# clouds_v30.net
KiCad netlist of a schematic drawn in EAGLE
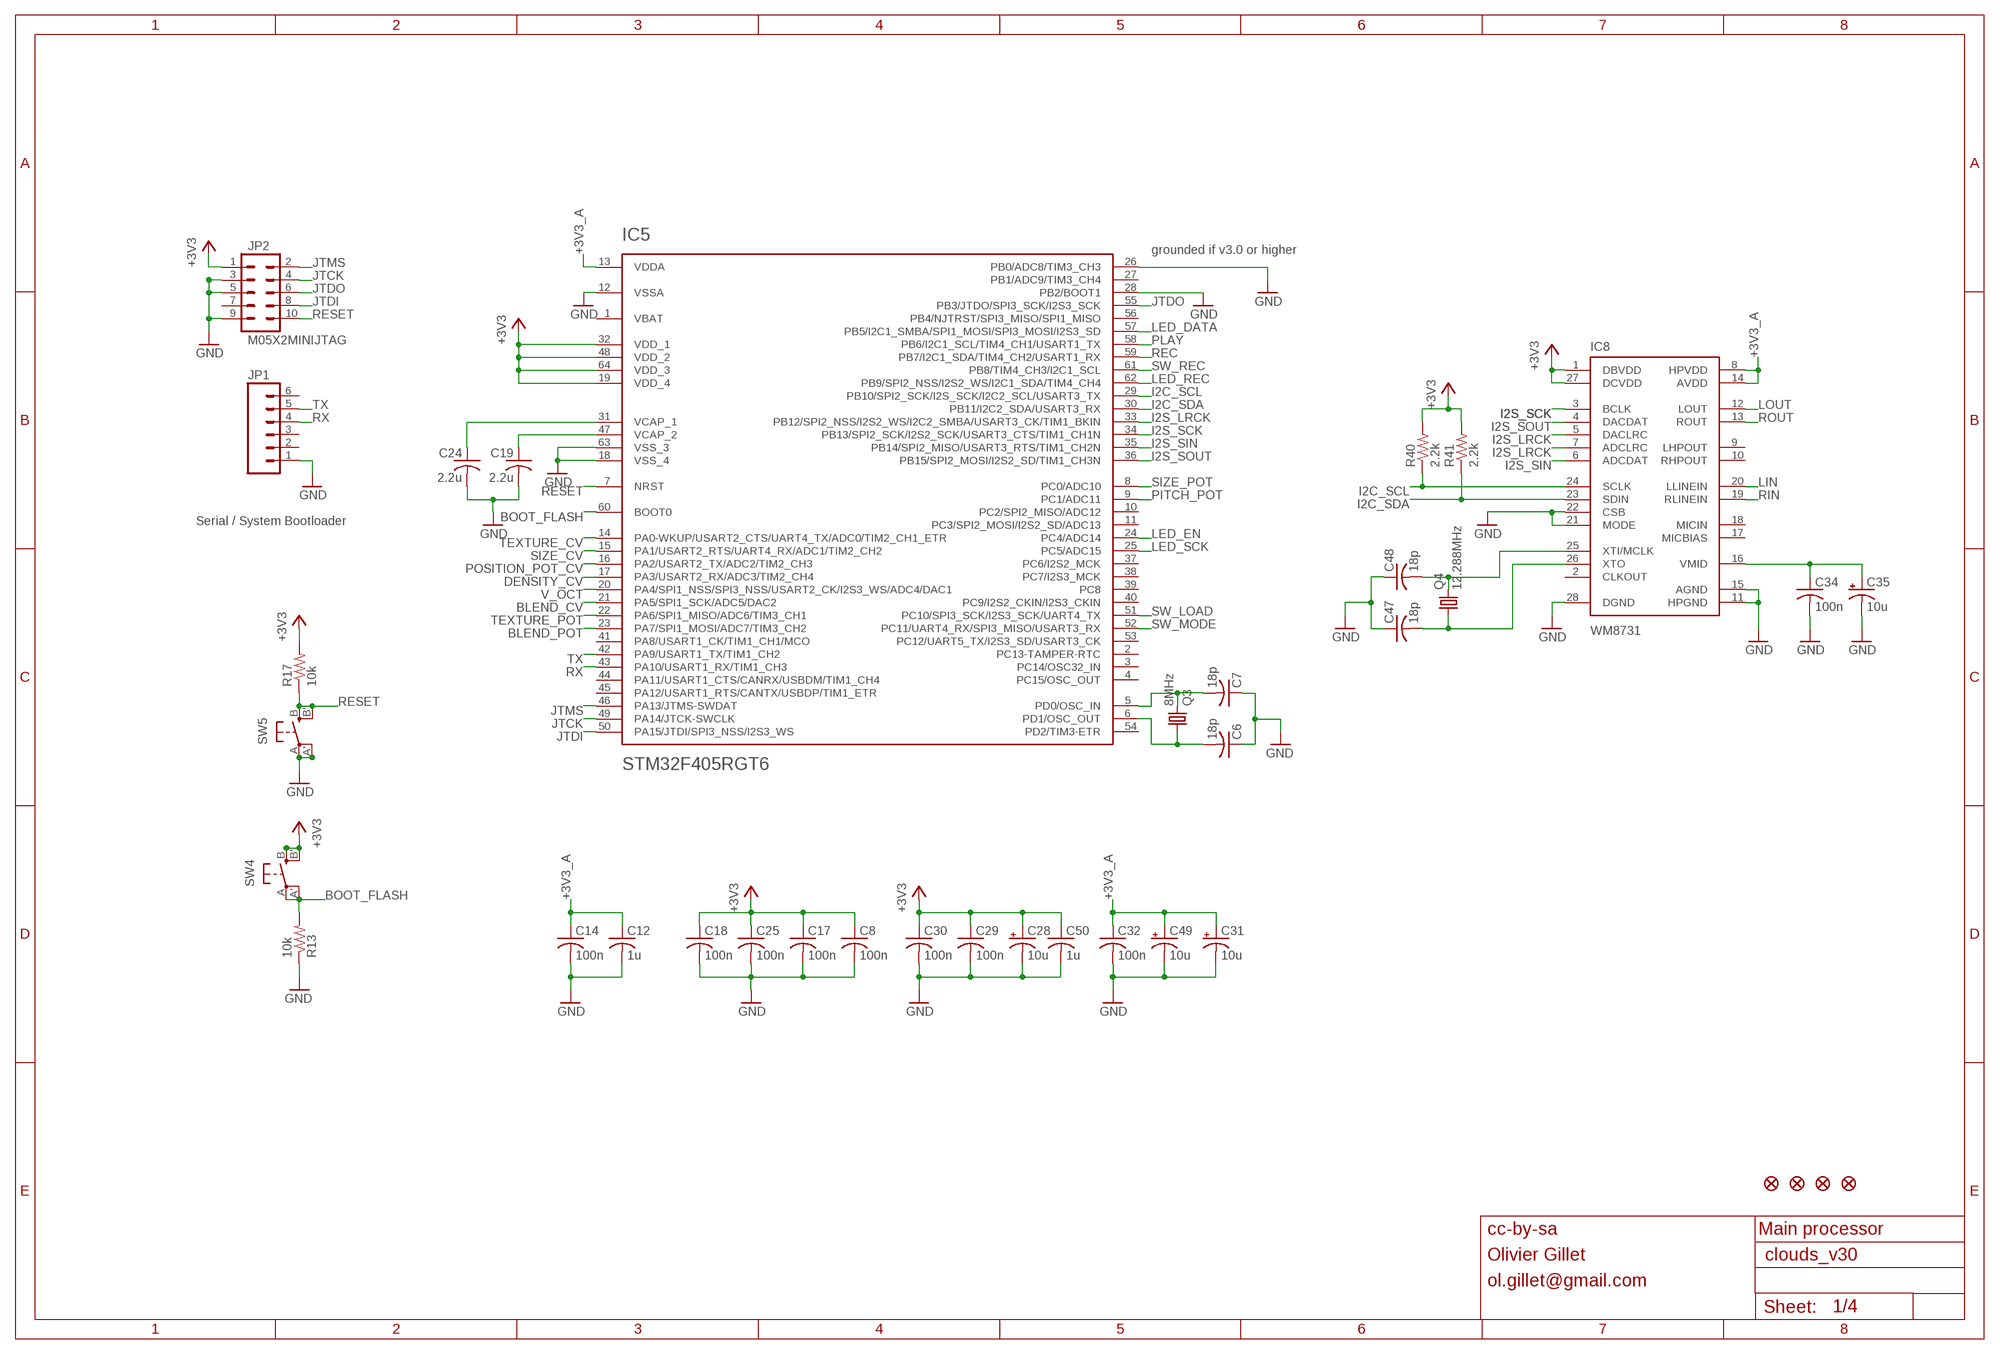
[diagram p0: schematic, sheet 1]
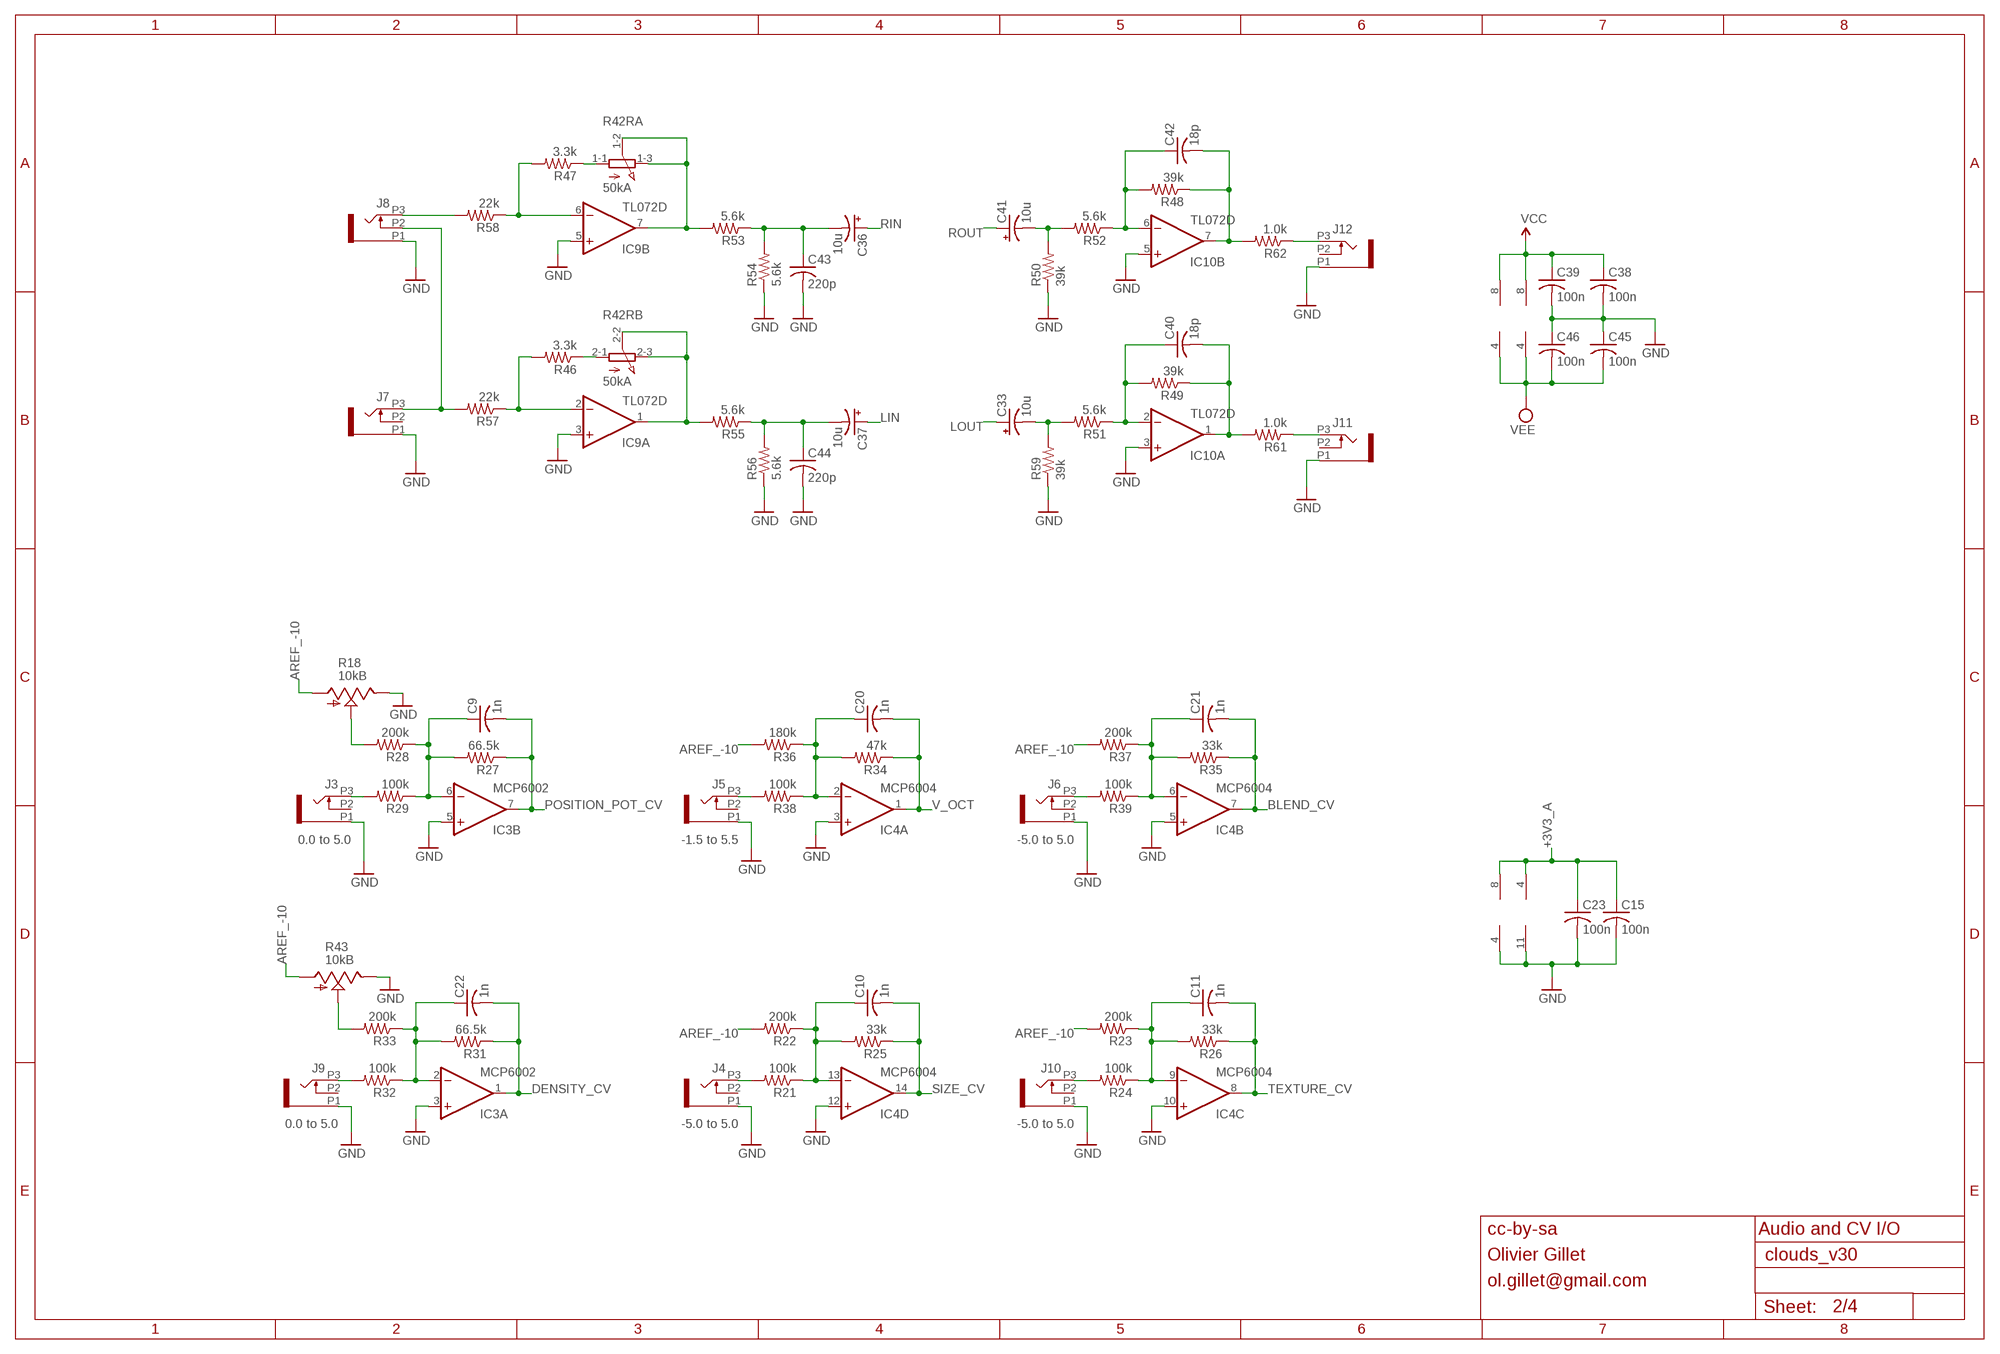
[diagram p1: schematic, sheet 2]
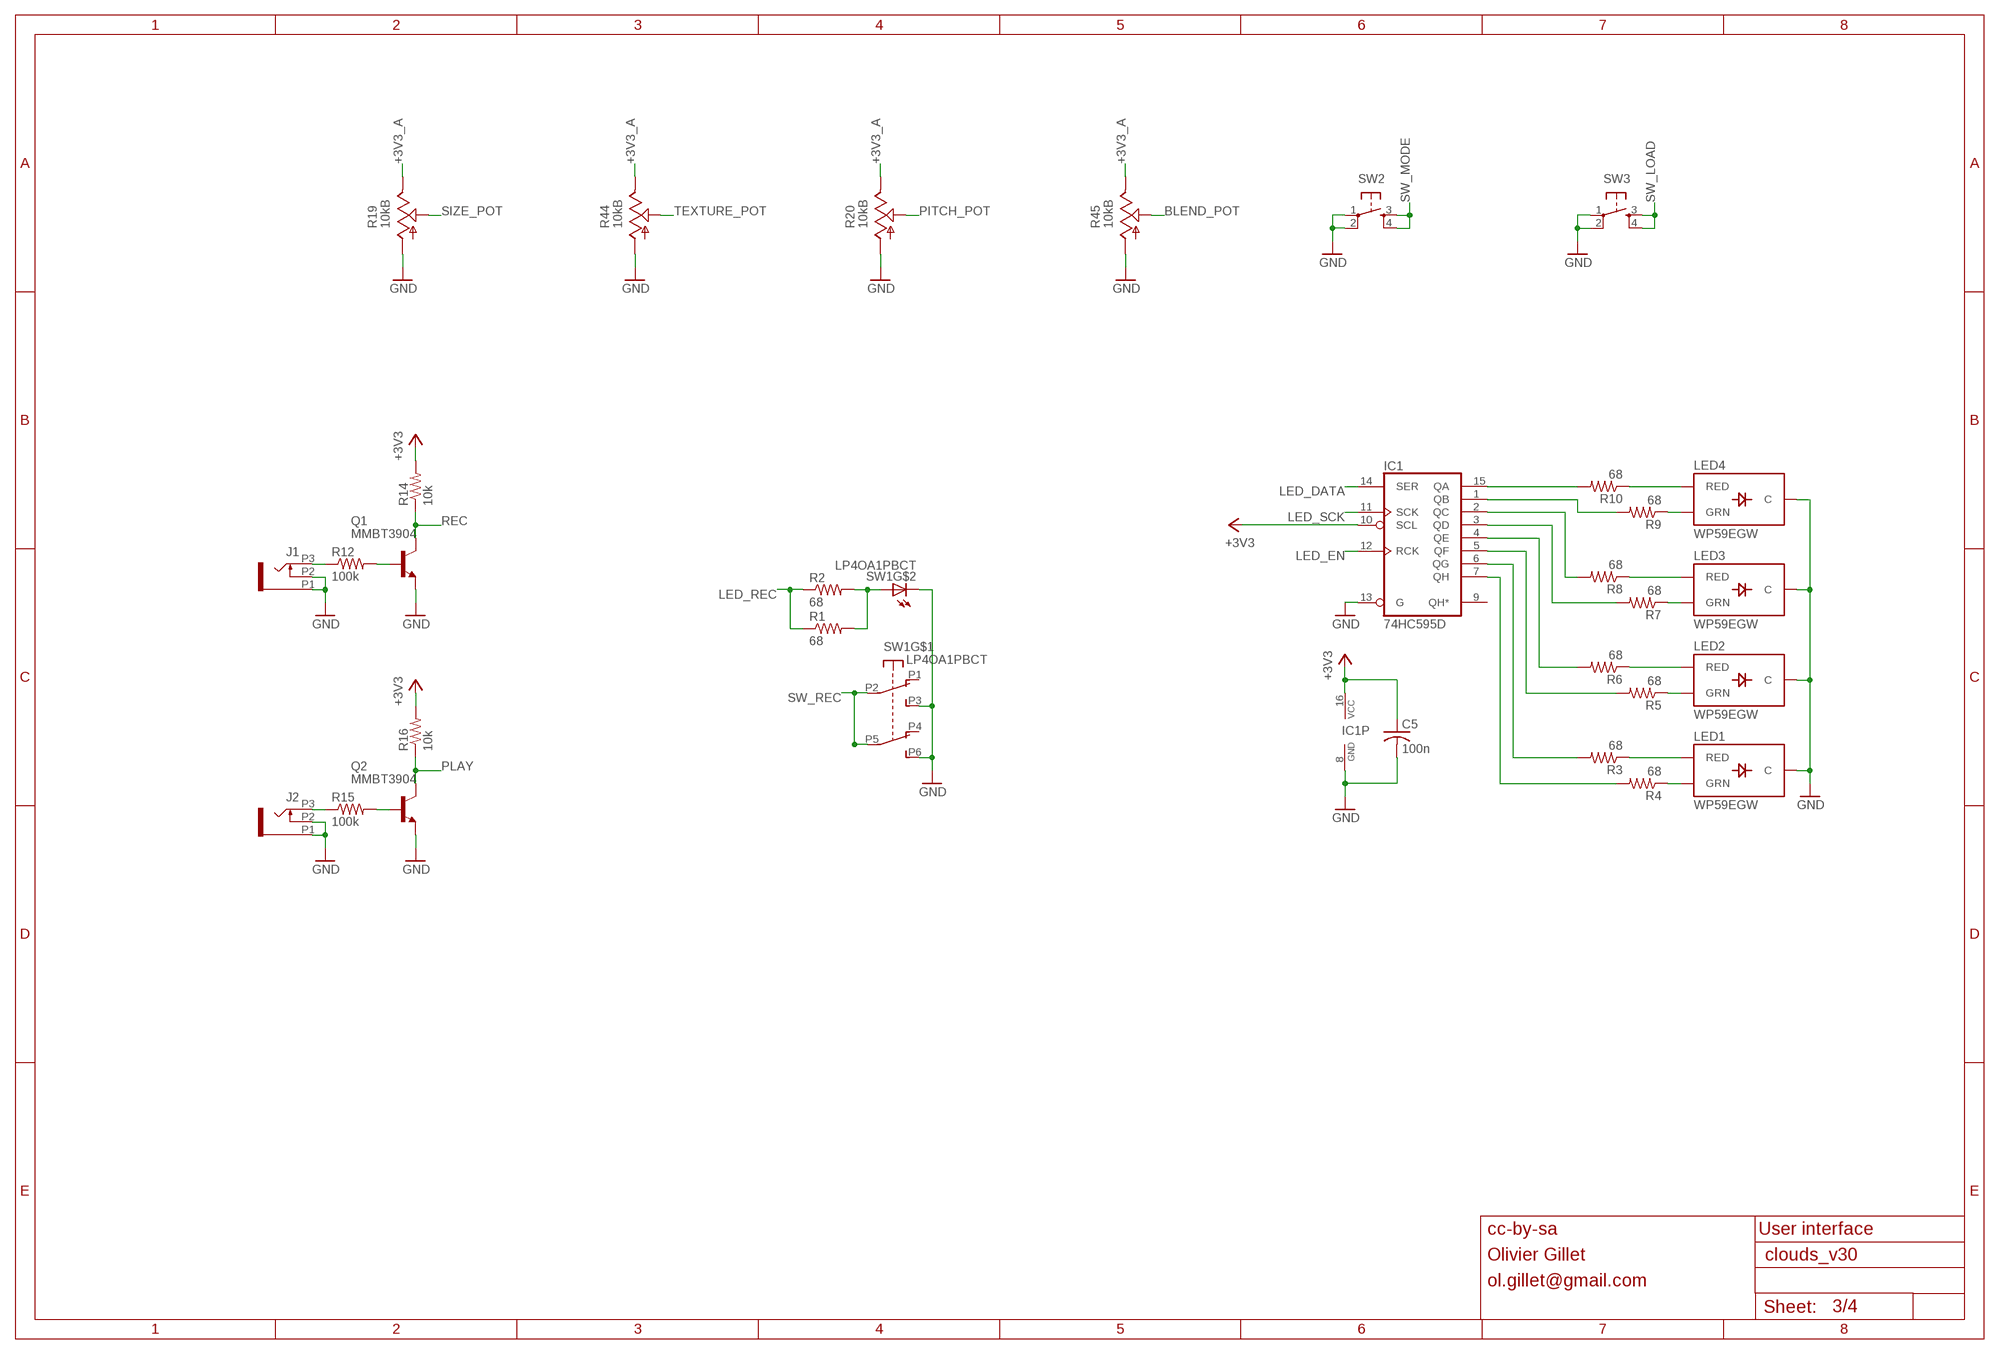
[diagram p2: schematic, sheet 3]
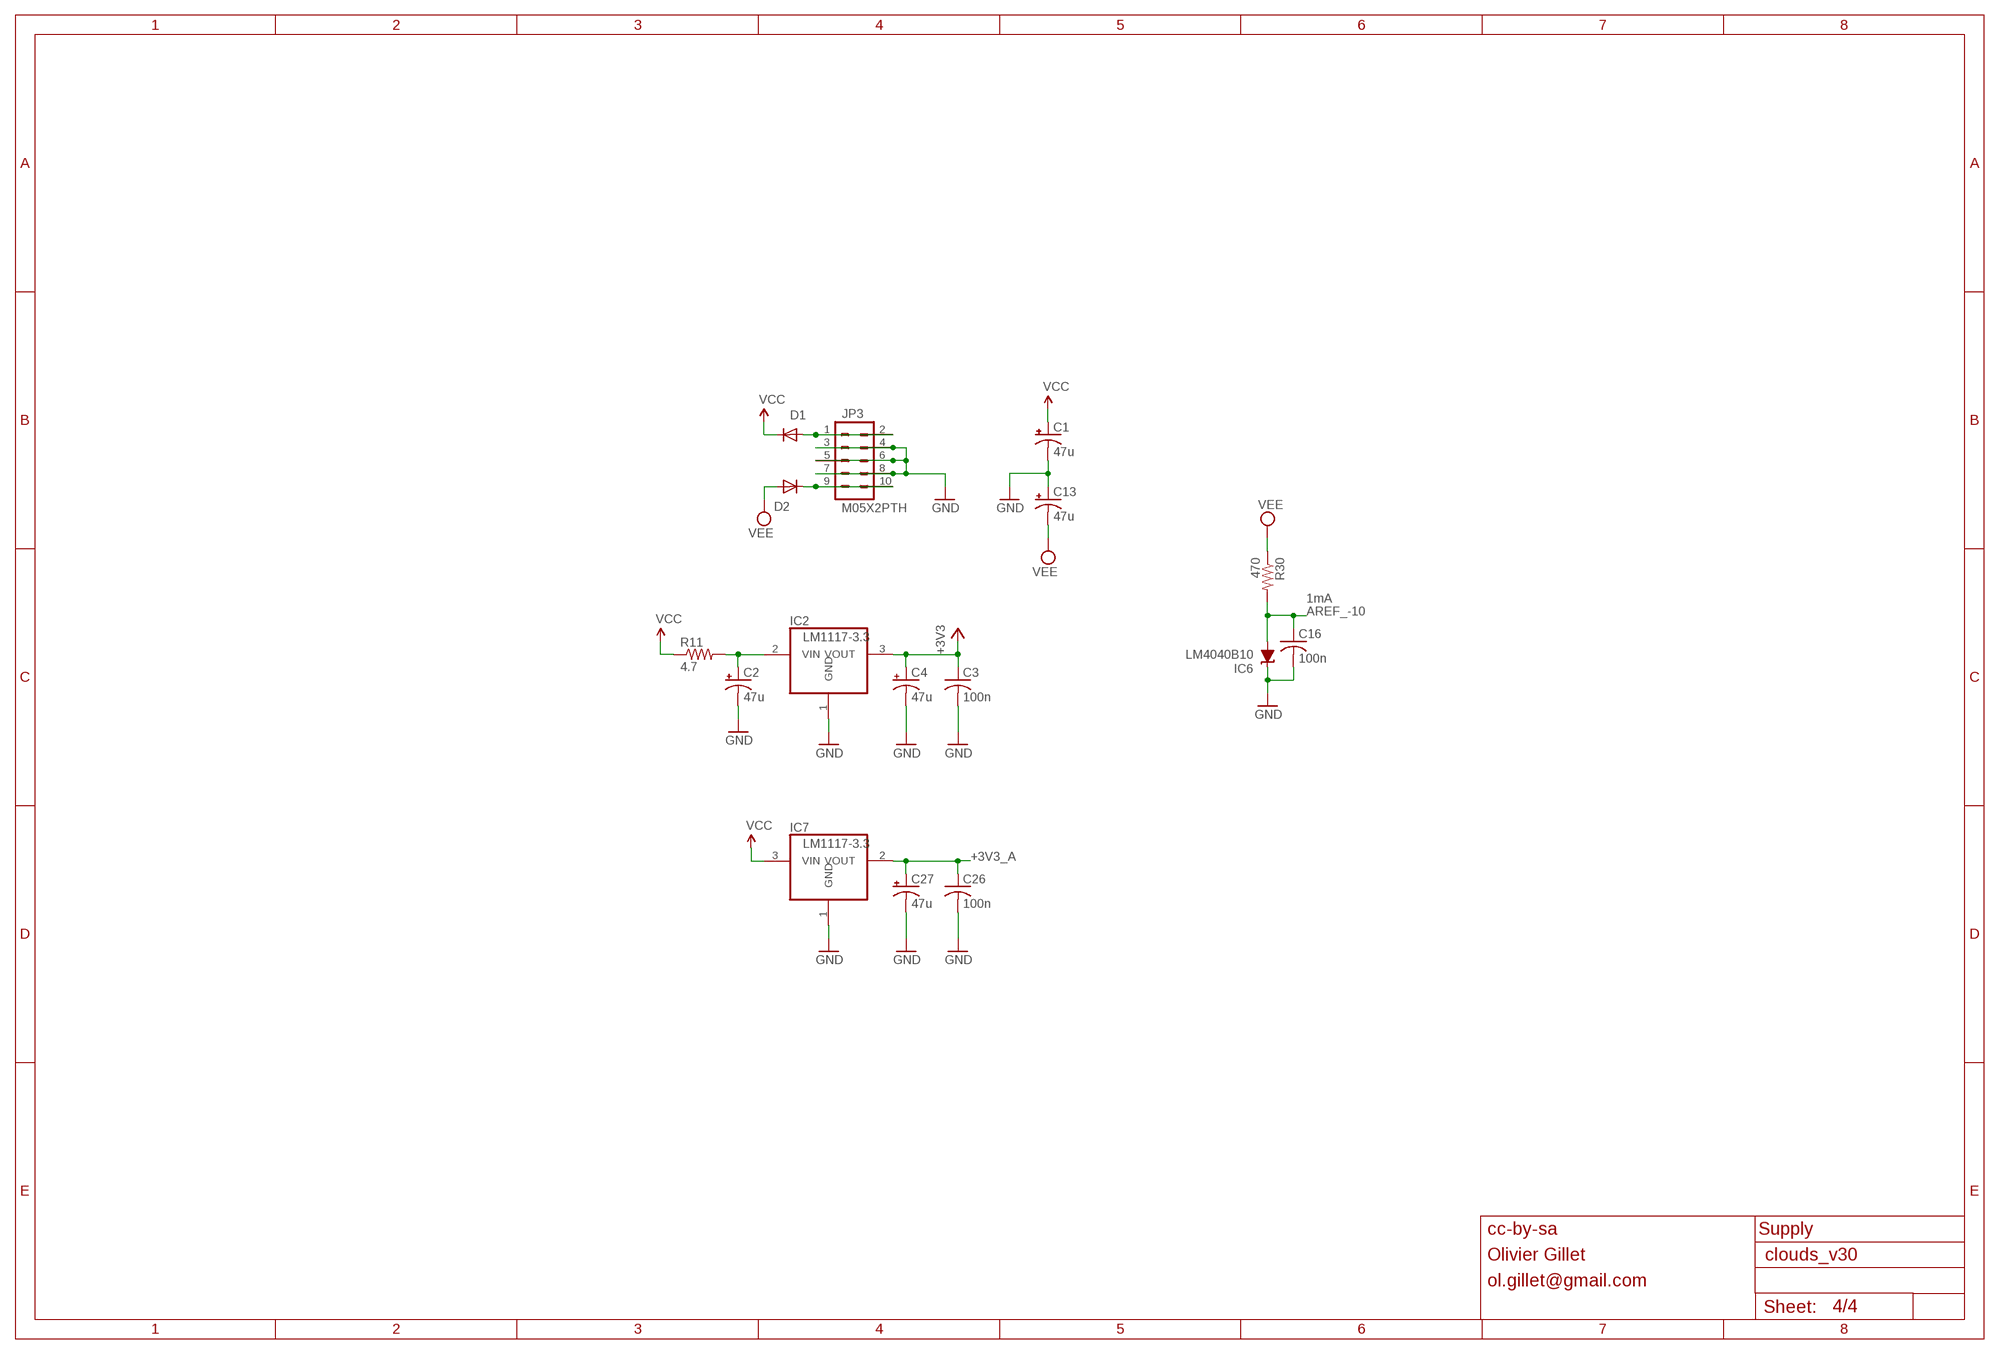
[diagram p3: schematic, sheet 4]

(export (version "E")
  (design (tool "Eeschema 10.0.6"))
  (components
    (comp (ref "C9")
      (value "1n")
      (footprint "eagle-import:C0603")
      (libsource (lib "eagle-import") (part "C-USC0603"))
    )
    (comp (ref "C10")
      (value "1n")
      (footprint "eagle-import:C0603")
      (libsource (lib "eagle-import") (part "C-USC0603"))
    )
    (comp (ref "C11")
      (value "1n")
      (footprint "eagle-import:C0603")
      (libsource (lib "eagle-import") (part "C-USC0603"))
    )
    (comp (ref "C15")
      (value "100n")
      (footprint "eagle-import:C0603")
      (libsource (lib "eagle-import") (part "C-USC0603"))
    )
    (comp (ref "C20")
      (value "1n")
      (footprint "eagle-import:C0603")
      (libsource (lib "eagle-import") (part "C-USC0603"))
    )
    (comp (ref "C21")
      (value "1n")
      (footprint "eagle-import:C0603")
      (libsource (lib "eagle-import") (part "C-USC0603"))
    )
    (comp (ref "C22")
      (value "1n")
      (footprint "eagle-import:C0603")
      (libsource (lib "eagle-import") (part "C-USC0603"))
    )
    (comp (ref "C23")
      (value "100n")
      (footprint "eagle-import:C0603")
      (libsource (lib "eagle-import") (part "C-USC0603"))
    )
    (comp (ref "C33")
      (value "10u")
      (footprint "eagle-import:PANASONIC_B")
      (libsource (lib "eagle-import") (part "CPOL-USB"))
    )
    (comp (ref "C36")
      (value "10u")
      (footprint "eagle-import:PANASONIC_B")
      (libsource (lib "eagle-import") (part "CPOL-USB"))
    )
    (comp (ref "C37")
      (value "10u")
      (footprint "eagle-import:PANASONIC_B")
      (libsource (lib "eagle-import") (part "CPOL-USB"))
    )
    (comp (ref "C38")
      (value "100n")
      (footprint "eagle-import:C0603")
      (libsource (lib "eagle-import") (part "C-USC0603"))
    )
    (comp (ref "C39")
      (value "100n")
      (footprint "eagle-import:C0603")
      (libsource (lib "eagle-import") (part "C-USC0603"))
    )
    (comp (ref "C40")
      (value "18p")
      (footprint "eagle-import:C0603")
      (libsource (lib "eagle-import") (part "C-USC0603"))
    )
    (comp (ref "C41")
      (value "10u")
      (footprint "eagle-import:PANASONIC_B")
      (libsource (lib "eagle-import") (part "CPOL-USB"))
    )
    (comp (ref "C42")
      (value "18p")
      (footprint "eagle-import:C0603")
      (libsource (lib "eagle-import") (part "C-USC0603"))
    )
    (comp (ref "C43")
      (value "220p")
      (footprint "eagle-import:C0603")
      (libsource (lib "eagle-import") (part "C-USC0603"))
    )
    (comp (ref "C44")
      (value "220p")
      (footprint "eagle-import:C0603")
      (libsource (lib "eagle-import") (part "C-USC0603"))
    )
    (comp (ref "C45")
      (value "100n")
      (footprint "eagle-import:C0603")
      (libsource (lib "eagle-import") (part "C-USC0603"))
    )
    (comp (ref "C46")
      (value "100n")
      (footprint "eagle-import:C0603")
      (libsource (lib "eagle-import") (part "C-USC0603"))
    )
    (comp (ref "IC3")
      (value "MCP6002")
      (footprint "eagle-import:SO08")
      (libsource (lib "eagle-import") (part "TL072D"))
    )
    (comp (ref "IC4")
      (value "MCP6004")
      (footprint "eagle-import:SO14")
      (libsource (lib "eagle-import") (part "TL074D"))
    )
    (comp (ref "IC9")
      (value "TL072D")
      (footprint "eagle-import:SO08")
      (libsource (lib "eagle-import") (part "og-linear_TL072D"))
    )
    (comp (ref "IC10")
      (value "TL072D")
      (footprint "eagle-import:SO08")
      (libsource (lib "eagle-import") (part "og-linear_TL072D"))
    )
    (comp (ref "J3")
      (value "PJ301_THONKICONN6")
      (footprint "eagle-import:WQP_PJ_301M6")
      (libsource (lib "eagle-import") (part "PJ301_THONKICONN6"))
    )
    (comp (ref "J4")
      (value "PJ301_THONKICONN6")
      (footprint "eagle-import:WQP_PJ_301M6")
      (libsource (lib "eagle-import") (part "PJ301_THONKICONN6"))
    )
    (comp (ref "J5")
      (value "PJ301_THONKICONN6")
      (footprint "eagle-import:WQP_PJ_301M6")
      (libsource (lib "eagle-import") (part "PJ301_THONKICONN6"))
    )
    (comp (ref "J6")
      (value "PJ301_THONKICONN6")
      (footprint "eagle-import:WQP_PJ_301M6")
      (libsource (lib "eagle-import") (part "PJ301_THONKICONN6"))
    )
    (comp (ref "J7")
      (value "PJ301_THONKICONN6")
      (footprint "eagle-import:WQP_PJ_301M6")
      (libsource (lib "eagle-import") (part "PJ301_THONKICONN6"))
    )
    (comp (ref "J8")
      (value "PJ301_THONKICONN6")
      (footprint "eagle-import:WQP_PJ_301M6")
      (libsource (lib "eagle-import") (part "PJ301_THONKICONN6"))
    )
    (comp (ref "J9")
      (value "PJ301_THONKICONN6")
      (footprint "eagle-import:WQP_PJ_301M6")
      (libsource (lib "eagle-import") (part "PJ301_THONKICONN6"))
    )
    (comp (ref "J10")
      (value "PJ301_THONKICONN6")
      (footprint "eagle-import:WQP_PJ_301M6")
      (libsource (lib "eagle-import") (part "PJ301_THONKICONN6"))
    )
    (comp (ref "J11")
      (value "PJ301_THONKICONN6")
      (footprint "eagle-import:WQP_PJ_301M6")
      (libsource (lib "eagle-import") (part "PJ301_THONKICONN6"))
    )
    (comp (ref "J12")
      (value "PJ301_THONKICONN6")
      (footprint "eagle-import:WQP_PJ_301M6")
      (libsource (lib "eagle-import") (part "PJ301_THONKICONN6"))
    )
    (comp (ref "R18")
      (value "10kB")
      (footprint "eagle-import:ALPS_POT_VERTICAL_PS")
      (libsource (lib "eagle-import") (part "POT_USVERTICAL_PS"))
    )
    (comp (ref "R21")
      (value "100k")
      (footprint "eagle-import:R0603")
      (libsource (lib "eagle-import") (part "R-US_R0603"))
    )
    (comp (ref "R22")
      (value "200k")
      (footprint "eagle-import:R0603")
      (libsource (lib "eagle-import") (part "R-US_R0603"))
    )
    (comp (ref "R23")
      (value "200k")
      (footprint "eagle-import:R0603")
      (libsource (lib "eagle-import") (part "R-US_R0603"))
    )
    (comp (ref "R24")
      (value "100k")
      (footprint "eagle-import:R0603")
      (libsource (lib "eagle-import") (part "R-US_R0603"))
    )
    (comp (ref "R25")
      (value "33k")
      (footprint "eagle-import:R0603")
      (libsource (lib "eagle-import") (part "R-US_R0603"))
    )
    (comp (ref "R26")
      (value "33k")
      (footprint "eagle-import:R0603")
      (libsource (lib "eagle-import") (part "R-US_R0603"))
    )
    (comp (ref "R27")
      (value "66.5k")
      (footprint "eagle-import:R0603")
      (libsource (lib "eagle-import") (part "R-US_R0603"))
    )
    (comp (ref "R28")
      (value "200k")
      (footprint "eagle-import:R0603")
      (libsource (lib "eagle-import") (part "R-US_R0603"))
    )
    (comp (ref "R29")
      (value "100k")
      (footprint "eagle-import:R0603")
      (libsource (lib "eagle-import") (part "R-US_R0603"))
    )
    (comp (ref "R31")
      (value "66.5k")
      (footprint "eagle-import:R0603")
      (libsource (lib "eagle-import") (part "R-US_R0603"))
    )
    (comp (ref "R32")
      (value "100k")
      (footprint "eagle-import:R0603")
      (libsource (lib "eagle-import") (part "R-US_R0603"))
    )
    (comp (ref "R33")
      (value "200k")
      (footprint "eagle-import:R0603")
      (libsource (lib "eagle-import") (part "R-US_R0603"))
    )
    (comp (ref "R34")
      (value "47k")
      (footprint "eagle-import:R0603")
      (libsource (lib "eagle-import") (part "R-US_R0603"))
    )
    (comp (ref "R35")
      (value "33k")
      (footprint "eagle-import:R0603")
      (libsource (lib "eagle-import") (part "R-US_R0603"))
    )
    (comp (ref "R36")
      (value "180k")
      (footprint "eagle-import:R0603")
      (libsource (lib "eagle-import") (part "R-US_R0603"))
    )
    (comp (ref "R37")
      (value "200k")
      (footprint "eagle-import:R0603")
      (libsource (lib "eagle-import") (part "R-US_R0603"))
    )
    (comp (ref "R38")
      (value "100k")
      (footprint "eagle-import:R0603")
      (libsource (lib "eagle-import") (part "R-US_R0603"))
    )
    (comp (ref "R39")
      (value "100k")
      (footprint "eagle-import:R0603")
      (libsource (lib "eagle-import") (part "R-US_R0603"))
    )
    (comp (ref "R42")
      (value "50kA")
      (footprint "eagle-import:ALPHA_RD902F-040")
      (libsource (lib "eagle-import") (part "RD902F-040"))
    )
    (comp (ref "R43")
      (value "10kB")
      (footprint "eagle-import:ALPS_POT_VERTICAL_PS")
      (libsource (lib "eagle-import") (part "POT_USVERTICAL_PS"))
    )
    (comp (ref "R46")
      (value "3.3k")
      (footprint "eagle-import:R0603")
      (libsource (lib "eagle-import") (part "R-US_R0603"))
    )
    (comp (ref "R47")
      (value "3.3k")
      (footprint "eagle-import:R0603")
      (libsource (lib "eagle-import") (part "R-US_R0603"))
    )
    (comp (ref "R48")
      (value "39k")
      (footprint "eagle-import:R0603")
      (libsource (lib "eagle-import") (part "R-US_R0603"))
    )
    (comp (ref "R49")
      (value "39k")
      (footprint "eagle-import:R0603")
      (libsource (lib "eagle-import") (part "R-US_R0603"))
    )
    (comp (ref "R50")
      (value "39k")
      (footprint "eagle-import:R0603")
      (libsource (lib "eagle-import") (part "R-US_R0603"))
    )
    (comp (ref "R51")
      (value "5.6k")
      (footprint "eagle-import:R0603")
      (libsource (lib "eagle-import") (part "R-US_R0603"))
    )
    (comp (ref "R52")
      (value "5.6k")
      (footprint "eagle-import:R0603")
      (libsource (lib "eagle-import") (part "R-US_R0603"))
    )
    (comp (ref "R53")
      (value "5.6k")
      (footprint "eagle-import:R0603")
      (libsource (lib "eagle-import") (part "R-US_R0603"))
    )
    (comp (ref "R54")
      (value "5.6k")
      (footprint "eagle-import:R0603")
      (libsource (lib "eagle-import") (part "R-US_R0603"))
    )
    (comp (ref "R55")
      (value "5.6k")
      (footprint "eagle-import:R0603")
      (libsource (lib "eagle-import") (part "R-US_R0603"))
    )
    (comp (ref "R56")
      (value "5.6k")
      (footprint "eagle-import:R0603")
      (libsource (lib "eagle-import") (part "R-US_R0603"))
    )
    (comp (ref "R57")
      (value "22k")
      (footprint "eagle-import:R0603")
      (libsource (lib "eagle-import") (part "R-US_R0603"))
    )
    (comp (ref "R58")
      (value "22k")
      (footprint "eagle-import:R0603")
      (libsource (lib "eagle-import") (part "R-US_R0603"))
    )
    (comp (ref "R59")
      (value "39k")
      (footprint "eagle-import:R0603")
      (libsource (lib "eagle-import") (part "R-US_R0603"))
    )
    (comp (ref "R61")
      (value "1.0k")
      (footprint "eagle-import:R0603")
      (libsource (lib "eagle-import") (part "R-US_R0603"))
    )
    (comp (ref "R62")
      (value "1.0k")
      (footprint "eagle-import:R0603")
      (libsource (lib "eagle-import") (part "R-US_R0603"))
    )
    (comp (ref "C6")
      (value "18p")
      (footprint "eagle-import:C0603")
      (libsource (lib "eagle-import") (part "C-USC0603"))
    )
    (comp (ref "C7")
      (value "18p")
      (footprint "eagle-import:C0603")
      (libsource (lib "eagle-import") (part "C-USC0603"))
    )
    (comp (ref "C8")
      (value "100n")
      (footprint "eagle-import:C0603")
      (libsource (lib "eagle-import") (part "C-USC0603"))
    )
    (comp (ref "C12")
      (value "1u")
      (footprint "eagle-import:C0603")
      (libsource (lib "eagle-import") (part "C-USC0603"))
    )
    (comp (ref "C14")
      (value "100n")
      (footprint "eagle-import:C0603")
      (libsource (lib "eagle-import") (part "C-USC0603"))
    )
    (comp (ref "C17")
      (value "100n")
      (footprint "eagle-import:C0603")
      (libsource (lib "eagle-import") (part "C-USC0603"))
    )
    (comp (ref "C18")
      (value "100n")
      (footprint "eagle-import:C0603")
      (libsource (lib "eagle-import") (part "C-USC0603"))
    )
    (comp (ref "C19")
      (value "2.2u")
      (footprint "eagle-import:C0805")
      (libsource (lib "eagle-import") (part "C-USC0805"))
    )
    (comp (ref "C24")
      (value "2.2u")
      (footprint "eagle-import:C0805")
      (libsource (lib "eagle-import") (part "C-USC0805"))
    )
    (comp (ref "C25")
      (value "100n")
      (footprint "eagle-import:C0603")
      (libsource (lib "eagle-import") (part "C-USC0603"))
    )
    (comp (ref "C28")
      (value "10u")
      (footprint "eagle-import:PANASONIC_A")
      (libsource (lib "eagle-import") (part "CPOL-USA"))
    )
    (comp (ref "C29")
      (value "100n")
      (footprint "eagle-import:C0603")
      (libsource (lib "eagle-import") (part "C-USC0603"))
    )
    (comp (ref "C30")
      (value "100n")
      (footprint "eagle-import:C0603")
      (libsource (lib "eagle-import") (part "C-USC0603"))
    )
    (comp (ref "C31")
      (value "10u")
      (footprint "eagle-import:PANASONIC_B")
      (libsource (lib "eagle-import") (part "CPOL-USB"))
    )
    (comp (ref "C32")
      (value "100n")
      (footprint "eagle-import:C0603")
      (libsource (lib "eagle-import") (part "C-USC0603"))
    )
    (comp (ref "C34")
      (value "100n")
      (footprint "eagle-import:C0603")
      (libsource (lib "eagle-import") (part "C-USC0603"))
    )
    (comp (ref "C35")
      (value "10u")
      (footprint "eagle-import:PANASONIC_B")
      (libsource (lib "eagle-import") (part "CPOL-USB"))
    )
    (comp (ref "C47")
      (value "18p")
      (footprint "eagle-import:C0603")
      (libsource (lib "eagle-import") (part "C-USC0603"))
    )
    (comp (ref "C48")
      (value "18p")
      (footprint "eagle-import:C0603")
      (libsource (lib "eagle-import") (part "C-USC0603"))
    )
    (comp (ref "C49")
      (value "10u")
      (footprint "eagle-import:PANASONIC_A")
      (libsource (lib "eagle-import") (part "CPOL-USA"))
    )
    (comp (ref "C50")
      (value "1u")
      (footprint "eagle-import:C0603")
      (libsource (lib "eagle-import") (part "C-USC0603"))
    )
    (comp (ref "F1")
      (value "FIDUCIAL1X2")
      (footprint "eagle-import:FIDUCIAL-1X2")
      (libsource (lib "eagle-import") (part "FIDUCIAL1X2"))
    )
    (comp (ref "F2")
      (value "FIDUCIAL1X2")
      (footprint "eagle-import:FIDUCIAL-1X2")
      (libsource (lib "eagle-import") (part "FIDUCIAL1X2"))
    )
    (comp (ref "F3")
      (value "FIDUCIAL1X2")
      (footprint "eagle-import:FIDUCIAL-1X2")
      (libsource (lib "eagle-import") (part "FIDUCIAL1X2"))
    )
    (comp (ref "F4")
      (value "FIDUCIAL1X2")
      (footprint "eagle-import:FIDUCIAL-1X2")
      (libsource (lib "eagle-import") (part "FIDUCIAL1X2"))
    )
    (comp (ref "IC5")
      (value "STM32F405RGT6")
      (footprint "eagle-import:TQFP-10X10-64")
      (libsource (lib "eagle-import") (part "STM32F20X"))
    )
    (comp (ref "IC8")
      (value "WM8731")
      (footprint "eagle-import:SSOP28")
      (libsource (lib "eagle-import") (part "WM8731"))
    )
    (comp (ref "JP1")
      (value "M06SIP")
      (footprint "eagle-import:1X06")
      (libsource (lib "eagle-import") (part "M06SIP"))
    )
    (comp (ref "JP2")
      (value "M05X2MINIJTAG")
      (footprint "eagle-import:2X5-1.27")
      (libsource (lib "eagle-import") (part "M05X2MINIJTAG"))
    )
    (comp (ref "Q3")
      (value "8MHz")
      (footprint "eagle-import:HC49UP")
      (libsource (lib "eagle-import") (part "CRYSTALHC49UP"))
    )
    (comp (ref "Q4")
      (value "12.288MHz")
      (footprint "eagle-import:HC49UP")
      (libsource (lib "eagle-import") (part "CRYSTALHC49UP"))
    )
    (comp (ref "R13")
      (value "10k")
      (footprint "eagle-import:R0603")
      (libsource (lib "eagle-import") (part "R-US_R0603"))
    )
    (comp (ref "R17")
      (value "10k")
      (footprint "eagle-import:R0603")
      (libsource (lib "eagle-import") (part "R-US_R0603"))
    )
    (comp (ref "R40")
      (value "2.2k")
      (footprint "eagle-import:R0603")
      (libsource (lib "eagle-import") (part "R-US_R0603"))
    )
    (comp (ref "R41")
      (value "2.2k")
      (footprint "eagle-import:R0603")
      (libsource (lib "eagle-import") (part "R-US_R0603"))
    )
    (comp (ref "SW4")
      (value "EVQQ2")
      (footprint "eagle-import:EVQ-Q2")
      (libsource (lib "eagle-import") (part "EVQQ2"))
    )
    (comp (ref "SW5")
      (value "EVQQ2")
      (footprint "eagle-import:EVQ-Q2")
      (libsource (lib "eagle-import") (part "EVQQ2"))
    )
    (comp (ref "C1")
      (value "47u")
      (footprint "eagle-import:PANASONIC_D")
      (libsource (lib "eagle-import") (part "CPOL-USD"))
    )
    (comp (ref "C2")
      (value "47u")
      (footprint "eagle-import:PANASONIC_D")
      (libsource (lib "eagle-import") (part "CPOL-USD"))
    )
    (comp (ref "C3")
      (value "100n")
      (footprint "eagle-import:C0603")
      (libsource (lib "eagle-import") (part "C-USC0603"))
    )
    (comp (ref "C4")
      (value "47u")
      (footprint "eagle-import:PANASONIC_D")
      (libsource (lib "eagle-import") (part "CPOL-USD"))
    )
    (comp (ref "C13")
      (value "47u")
      (footprint "eagle-import:PANASONIC_D")
      (libsource (lib "eagle-import") (part "CPOL-USD"))
    )
    (comp (ref "C16")
      (value "100n")
      (footprint "eagle-import:C0603")
      (libsource (lib "eagle-import") (part "C-USC0603"))
    )
    (comp (ref "C26")
      (value "100n")
      (footprint "eagle-import:C0603")
      (libsource (lib "eagle-import") (part "C-USC0603"))
    )
    (comp (ref "C27")
      (value "47u")
      (footprint "eagle-import:PANASONIC_D")
      (libsource (lib "eagle-import") (part "CPOL-USD"))
    )
    (comp (ref "D1")
      (value "1N5819HW")
      (footprint "eagle-import:SOD123")
      (libsource (lib "eagle-import") (part "DIODE-SOD123"))
    )
    (comp (ref "D2")
      (value "1N5819HW")
      (footprint "eagle-import:SOD123")
      (libsource (lib "eagle-import") (part "DIODE-SOD123"))
    )
    (comp (ref "IC2")
      (value "LM1117-3.3")
      (footprint "eagle-import:TO252")
      (libsource (lib "eagle-import") (part "REG1117T"))
    )
    (comp (ref "IC6")
      (value "LM4040B10")
      (footprint "eagle-import:DBZ_R-PDSO-G3")
      (libsource (lib "eagle-import") (part "LM4041DBZB12"))
    )
    (comp (ref "IC7")
      (value "LM1117-3.3")
      (footprint "eagle-import:SOT223")
      (libsource (lib "eagle-import") (part "REG1117"))
    )
    (comp (ref "JP3")
      (value "M05X2PTH")
      (footprint "eagle-import:AVR_ICSP")
      (libsource (lib "eagle-import") (part "M05X2PTH"))
    )
    (comp (ref "R11")
      (value "4.7")
      (footprint "eagle-import:R1206")
      (libsource (lib "eagle-import") (part "R-US_R1206"))
    )
    (comp (ref "R30")
      (value "470")
      (footprint "eagle-import:R0603")
      (libsource (lib "eagle-import") (part "R-US_R0603"))
    )
    (comp (ref "C5")
      (value "100n")
      (footprint "eagle-import:C0603")
      (libsource (lib "eagle-import") (part "C-USC0603"))
    )
    (comp (ref "IC1")
      (value "74HC595D")
      (footprint "eagle-import:SO16")
      (libsource (lib "eagle-import") (part "74595DHC"))
    )
    (comp (ref "J1")
      (value "PJ301_THONKICONN6")
      (footprint "eagle-import:WQP_PJ_301M6")
      (libsource (lib "eagle-import") (part "PJ301_THONKICONN6"))
    )
    (comp (ref "J2")
      (value "PJ301_THONKICONN6")
      (footprint "eagle-import:WQP_PJ_301M6")
      (libsource (lib "eagle-import") (part "PJ301_THONKICONN6"))
    )
    (comp (ref "LED1")
      (value "WP59EGW")
      (footprint "eagle-import:LED-BICOLOR-THROUGHHOLE-5MM")
      (libsource (lib "eagle-import") (part "LED-BICOLOR-THROUGHHOLE5MM"))
    )
    (comp (ref "LED2")
      (value "WP59EGW")
      (footprint "eagle-import:LED-BICOLOR-THROUGHHOLE-5MM")
      (libsource (lib "eagle-import") (part "LED-BICOLOR-THROUGHHOLE5MM"))
    )
    (comp (ref "LED3")
      (value "WP59EGW")
      (footprint "eagle-import:LED-BICOLOR-THROUGHHOLE-5MM")
      (libsource (lib "eagle-import") (part "LED-BICOLOR-THROUGHHOLE5MM"))
    )
    (comp (ref "LED4")
      (value "WP59EGW")
      (footprint "eagle-import:LED-BICOLOR-THROUGHHOLE-5MM")
      (libsource (lib "eagle-import") (part "LED-BICOLOR-THROUGHHOLE5MM"))
    )
    (comp (ref "Q1")
      (value "MMBT3904")
      (footprint "eagle-import:SOT23-BEC")
      (libsource (lib "eagle-import") (part "-NPN-SOT23-BECMMBT3904LT1"))
    )
    (comp (ref "Q2")
      (value "MMBT3904")
      (footprint "eagle-import:SOT23-BEC")
      (libsource (lib "eagle-import") (part "-NPN-SOT23-BECMMBT3904LT1"))
    )
    (comp (ref "R1")
      (value "68")
      (footprint "eagle-import:R0603")
      (libsource (lib "eagle-import") (part "R-US_R0603"))
    )
    (comp (ref "R2")
      (value "68")
      (footprint "eagle-import:R0603")
      (libsource (lib "eagle-import") (part "R-US_R0603"))
    )
    (comp (ref "R3")
      (value "68")
      (footprint "eagle-import:R0603")
      (libsource (lib "eagle-import") (part "R-US_R0603"))
    )
    (comp (ref "R4")
      (value "68")
      (footprint "eagle-import:R0603")
      (libsource (lib "eagle-import") (part "R-US_R0603"))
    )
    (comp (ref "R5")
      (value "68")
      (footprint "eagle-import:R0603")
      (libsource (lib "eagle-import") (part "R-US_R0603"))
    )
    (comp (ref "R6")
      (value "68")
      (footprint "eagle-import:R0603")
      (libsource (lib "eagle-import") (part "R-US_R0603"))
    )
    (comp (ref "R7")
      (value "68")
      (footprint "eagle-import:R0603")
      (libsource (lib "eagle-import") (part "R-US_R0603"))
    )
    (comp (ref "R8")
      (value "68")
      (footprint "eagle-import:R0603")
      (libsource (lib "eagle-import") (part "R-US_R0603"))
    )
    (comp (ref "R9")
      (value "68")
      (footprint "eagle-import:R0603")
      (libsource (lib "eagle-import") (part "R-US_R0603"))
    )
    (comp (ref "R10")
      (value "68")
      (footprint "eagle-import:R0603")
      (libsource (lib "eagle-import") (part "R-US_R0603"))
    )
    (comp (ref "R12")
      (value "100k")
      (footprint "eagle-import:R0603")
      (libsource (lib "eagle-import") (part "R-US_R0603"))
    )
    (comp (ref "R14")
      (value "10k")
      (footprint "eagle-import:R0603")
      (libsource (lib "eagle-import") (part "R-US_R0603"))
    )
    (comp (ref "R15")
      (value "100k")
      (footprint "eagle-import:R0603")
      (libsource (lib "eagle-import") (part "R-US_R0603"))
    )
    (comp (ref "R16")
      (value "10k")
      (footprint "eagle-import:R0603")
      (libsource (lib "eagle-import") (part "R-US_R0603"))
    )
    (comp (ref "R19")
      (value "10kB")
      (footprint "eagle-import:ALPS_POT_VERTICAL_PS")
      (libsource (lib "eagle-import") (part "POT_USVERTICAL_PS"))
    )
    (comp (ref "R20")
      (value "10kB")
      (footprint "eagle-import:ALPS_POT_VERTICAL_PS")
      (libsource (lib "eagle-import") (part "POT_USVERTICAL_PS"))
    )
    (comp (ref "R44")
      (value "10kB")
      (footprint "eagle-import:ALPS_POT_VERTICAL_PS")
      (libsource (lib "eagle-import") (part "POT_USVERTICAL_PS"))
    )
    (comp (ref "R45")
      (value "10kB")
      (footprint "eagle-import:ALPS_POT_VERTICAL_PS")
      (libsource (lib "eagle-import") (part "POT_USVERTICAL_PS"))
    )
    (comp (ref "SW1")
      (value "LP4OA1PBCT")
      (footprint "eagle-import:LP4OA1PBCT")
      (libsource (lib "eagle-import") (part "LP4OA1PBCT"))
    )
    (comp (ref "SW2")
      (value "TAC_SWITCHPTH")
      (footprint "eagle-import:TACTILE-PTH")
      (libsource (lib "eagle-import") (part "TAC_SWITCHPTH"))
    )
    (comp (ref "SW3")
      (value "TAC_SWITCHPTH")
      (footprint "eagle-import:TACTILE-PTH")
      (libsource (lib "eagle-import") (part "TAC_SWITCHPTH"))
    )
  )
  (nets
    (net (code "1") (name "+3V3") (class "Default")
      (node (ref "C17") (pin "1") (pinfunction "1_1") (pintype "passive"))
      (node (ref "C18") (pin "1") (pinfunction "1_1") (pintype "passive"))
      (node (ref "C25") (pin "1") (pinfunction "1_1") (pintype "passive"))
      (node (ref "C28") (pin "+") (pinfunction "+_+") (pintype "passive"))
      (node (ref "C29") (pin "1") (pinfunction "1_1") (pintype "passive"))
      (node (ref "C3") (pin "1") (pinfunction "1_1") (pintype "passive"))
      (node (ref "C30") (pin "1") (pinfunction "1_1") (pintype "passive"))
      (node (ref "C4") (pin "+") (pinfunction "+_+") (pintype "passive"))
      (node (ref "C5") (pin "1") (pinfunction "1_1") (pintype "passive"))
      (node (ref "C50") (pin "1") (pinfunction "1_1") (pintype "passive"))
      (node (ref "C8") (pin "1") (pinfunction "1_1") (pintype "passive"))
      (node (ref "IC1") (pin "10") (pinfunction "SCL_10") (pintype "input"))
      (node (ref "IC1") (pin "16") (pinfunction "VCC_16") (pintype "power_in"))
      (node (ref "IC2") (pin "3") (pinfunction "VOUT_3") (pintype "output"))
      (node (ref "IC5") (pin "19") (pinfunction "VDD_4_19") (pintype "power_in"))
      (node (ref "IC5") (pin "32") (pinfunction "VDD_1_32") (pintype "power_in"))
      (node (ref "IC5") (pin "48") (pinfunction "VDD_2_48") (pintype "power_in"))
      (node (ref "IC5") (pin "64") (pinfunction "VDD_3_64") (pintype "power_in"))
      (node (ref "IC8") (pin "1") (pinfunction "DBVDD_1") (pintype "bidirectional"))
      (node (ref "IC8") (pin "27") (pinfunction "DCVDD_27") (pintype "bidirectional"))
      (node (ref "JP2") (pin "1") (pinfunction "1_1") (pintype "passive"))
      (node (ref "R14") (pin "2") (pinfunction "2_2") (pintype "passive"))
      (node (ref "R16") (pin "2") (pinfunction "2_2") (pintype "passive"))
      (node (ref "R17") (pin "2") (pinfunction "2_2") (pintype "passive"))
      (node (ref "R40") (pin "2") (pinfunction "2_2") (pintype "passive"))
      (node (ref "R41") (pin "2") (pinfunction "2_2") (pintype "passive"))
      (node (ref "SW4") (pin "B") (pinfunction "S_B") (pintype "passive"))
      (node (ref "SW4") (pin "B'") (pinfunction "S1_B'") (pintype "passive"))
    )
    (net (code "2") (name "+3V3_A") (class "Default")
      (node (ref "C12") (pin "1") (pinfunction "1_1") (pintype "passive"))
      (node (ref "C14") (pin "1") (pinfunction "1_1") (pintype "passive"))
      (node (ref "C15") (pin "1") (pinfunction "1_1") (pintype "passive"))
      (node (ref "C23") (pin "1") (pinfunction "1_1") (pintype "passive"))
      (node (ref "C26") (pin "1") (pinfunction "1_1") (pintype "passive"))
      (node (ref "C27") (pin "+") (pinfunction "+_+") (pintype "passive"))
      (node (ref "C31") (pin "+") (pinfunction "+_+") (pintype "passive"))
      (node (ref "C32") (pin "1") (pinfunction "1_1") (pintype "passive"))
      (node (ref "C49") (pin "+") (pinfunction "+_+") (pintype "passive"))
      (node (ref "IC3") (pin "8") (pinfunction "V+_8") (pintype "power_in"))
      (node (ref "IC4") (pin "4") (pinfunction "V+_4") (pintype "power_in"))
      (node (ref "IC5") (pin "13") (pinfunction "VDDA_13") (pintype "power_in"))
      (node (ref "IC7") (pin "2") (pinfunction "VOUT_2") (pintype "output"))
      (node (ref "IC8") (pin "14") (pinfunction "AVDD_14") (pintype "bidirectional"))
      (node (ref "IC8") (pin "8") (pinfunction "HPVDD_8") (pintype "bidirectional"))
      (node (ref "R19") (pin "P$1") (pinfunction "E_P$1") (pintype "passive"))
      (node (ref "R20") (pin "P$1") (pinfunction "E_P$1") (pintype "passive"))
      (node (ref "R44") (pin "P$1") (pinfunction "E_P$1") (pintype "passive"))
      (node (ref "R45") (pin "P$1") (pinfunction "E_P$1") (pintype "passive"))
    )
    (net (code "3") (name "AREF_-10") (class "Default")
      (node (ref "C16") (pin "1") (pinfunction "1_1") (pintype "passive"))
      (node (ref "IC6") (pin "2") (pinfunction "A_2") (pintype "passive"))
      (node (ref "R18") (pin "P$3") (pinfunction "A_P$3") (pintype "passive"))
      (node (ref "R22") (pin "2") (pinfunction "2_2") (pintype "passive"))
      (node (ref "R23") (pin "2") (pinfunction "2_2") (pintype "passive"))
      (node (ref "R30") (pin "2") (pinfunction "2_2") (pintype "passive"))
      (node (ref "R36") (pin "2") (pinfunction "2_2") (pintype "passive"))
      (node (ref "R37") (pin "2") (pinfunction "2_2") (pintype "passive"))
      (node (ref "R43") (pin "P$3") (pinfunction "A_P$3") (pintype "passive"))
    )
    (net (code "4") (name "BLEND_CV") (class "Default")
      (node (ref "C21") (pin "2") (pinfunction "2_2") (pintype "passive"))
      (node (ref "IC4") (pin "7") (pinfunction "OUT_7") (pintype "output"))
      (node (ref "IC5") (pin "21") (pinfunction "PA5/SPI1_SCK/ADC5/DAC2_21") (pintype "bidirectional"))
      (node (ref "R35") (pin "1") (pinfunction "1_1") (pintype "passive"))
    )
    (net (code "5") (name "BLEND_POT") (class "Default")
      (node (ref "IC5") (pin "23") (pinfunction "PA7/SPI1_MOSI/ADC7/TIM3_CH2_23") (pintype "bidirectional"))
      (node (ref "R45") (pin "P$2") (pinfunction "S_P$2") (pintype "passive"))
    )
    (net (code "6") (name "BOOT_FLASH") (class "Default")
      (node (ref "IC5") (pin "60") (pinfunction "BOOT0_60") (pintype "bidirectional"))
      (node (ref "R13") (pin "2") (pinfunction "2_2") (pintype "passive"))
      (node (ref "SW4") (pin "A") (pinfunction "P_A") (pintype "passive"))
      (node (ref "SW4") (pin "A'") (pinfunction "P1_A'") (pintype "passive"))
    )
    (net (code "7") (name "DENSITY_CV") (class "Default")
      (node (ref "C22") (pin "2") (pinfunction "2_2") (pintype "passive"))
      (node (ref "IC3") (pin "1") (pinfunction "OUT_1") (pintype "output"))
      (node (ref "IC5") (pin "17") (pinfunction "PA3/USART2_RX/ADC3/TIM2_CH4_17") (pintype "bidirectional"))
      (node (ref "R31") (pin "1") (pinfunction "1_1") (pintype "passive"))
    )
    (net (code "8") (name "GND") (class "Default")
      (node (ref "C1") (pin "-") (pinfunction "-_-") (pintype "passive"))
      (node (ref "C12") (pin "2") (pinfunction "2_2") (pintype "passive"))
      (node (ref "C13") (pin "+") (pinfunction "+_+") (pintype "passive"))
      (node (ref "C14") (pin "2") (pinfunction "2_2") (pintype "passive"))
      (node (ref "C15") (pin "2") (pinfunction "2_2") (pintype "passive"))
      (node (ref "C16") (pin "2") (pinfunction "2_2") (pintype "passive"))
      (node (ref "C17") (pin "2") (pinfunction "2_2") (pintype "passive"))
      (node (ref "C18") (pin "2") (pinfunction "2_2") (pintype "passive"))
      (node (ref "C19") (pin "2") (pinfunction "2_2") (pintype "passive"))
      (node (ref "C2") (pin "-") (pinfunction "-_-") (pintype "passive"))
      (node (ref "C23") (pin "2") (pinfunction "2_2") (pintype "passive"))
      (node (ref "C24") (pin "2") (pinfunction "2_2") (pintype "passive"))
      (node (ref "C25") (pin "2") (pinfunction "2_2") (pintype "passive"))
      (node (ref "C26") (pin "2") (pinfunction "2_2") (pintype "passive"))
      (node (ref "C27") (pin "-") (pinfunction "-_-") (pintype "passive"))
      (node (ref "C28") (pin "-") (pinfunction "-_-") (pintype "passive"))
      (node (ref "C29") (pin "2") (pinfunction "2_2") (pintype "passive"))
      (node (ref "C3") (pin "2") (pinfunction "2_2") (pintype "passive"))
      (node (ref "C30") (pin "2") (pinfunction "2_2") (pintype "passive"))
      (node (ref "C31") (pin "-") (pinfunction "-_-") (pintype "passive"))
      (node (ref "C32") (pin "2") (pinfunction "2_2") (pintype "passive"))
      (node (ref "C34") (pin "2") (pinfunction "2_2") (pintype "passive"))
      (node (ref "C35") (pin "-") (pinfunction "-_-") (pintype "passive"))
      (node (ref "C38") (pin "2") (pinfunction "2_2") (pintype "passive"))
      (node (ref "C39") (pin "2") (pinfunction "2_2") (pintype "passive"))
      (node (ref "C4") (pin "-") (pinfunction "-_-") (pintype "passive"))
      (node (ref "C43") (pin "2") (pinfunction "2_2") (pintype "passive"))
      (node (ref "C44") (pin "2") (pinfunction "2_2") (pintype "passive"))
      (node (ref "C45") (pin "1") (pinfunction "1_1") (pintype "passive"))
      (node (ref "C46") (pin "1") (pinfunction "1_1") (pintype "passive"))
      (node (ref "C47") (pin "1") (pinfunction "1_1") (pintype "passive"))
      (node (ref "C48") (pin "1") (pinfunction "1_1") (pintype "passive"))
      (node (ref "C49") (pin "-") (pinfunction "-_-") (pintype "passive"))
      (node (ref "C5") (pin "2") (pinfunction "2_2") (pintype "passive"))
      (node (ref "C50") (pin "2") (pinfunction "2_2") (pintype "passive"))
      (node (ref "C6") (pin "1") (pinfunction "1_1") (pintype "passive"))
      (node (ref "C7") (pin "1") (pinfunction "1_1") (pintype "passive"))
      (node (ref "C8") (pin "2") (pinfunction "2_2") (pintype "passive"))
      (node (ref "IC1") (pin "13") (pinfunction "G_13") (pintype "input"))
      (node (ref "IC1") (pin "8") (pinfunction "GND_8") (pintype "power_in"))
      (node (ref "IC10") (pin "3") (pinfunction "+IN_3") (pintype "input"))
      (node (ref "IC10") (pin "5") (pinfunction "+IN_5") (pintype "input"))
      (node (ref "IC2") (pin "1") (pinfunction "GND_1") (pintype "power_in"))
      (node (ref "IC3") (pin "3") (pinfunction "+IN_3") (pintype "input"))
      (node (ref "IC3") (pin "4") (pinfunction "V-_4") (pintype "power_in"))
      (node (ref "IC3") (pin "5") (pinfunction "+IN_5") (pintype "input"))
      (node (ref "IC4") (pin "10") (pinfunction "+IN_10") (pintype "input"))
      (node (ref "IC4") (pin "11") (pinfunction "V-_11") (pintype "power_in"))
      (node (ref "IC4") (pin "12") (pinfunction "+IN_12") (pintype "input"))
      (node (ref "IC4") (pin "3") (pinfunction "+IN_3") (pintype "input"))
      (node (ref "IC4") (pin "5") (pinfunction "+IN_5") (pintype "input"))
      (node (ref "IC5") (pin "12") (pinfunction "VSSA_12") (pintype "power_in"))
      (node (ref "IC5") (pin "18") (pinfunction "VSS_4_18") (pintype "power_in"))
      (node (ref "IC5") (pin "26") (pinfunction "PB0/ADC8/TIM3_CH3_26") (pintype "bidirectional"))
      (node (ref "IC5") (pin "28") (pinfunction "PB2/BOOT1_28") (pintype "bidirectional"))
      (node (ref "IC5") (pin "63") (pinfunction "VSS_3_63") (pintype "power_in"))
      (node (ref "IC6") (pin "1") (pinfunction "C_1") (pintype "passive"))
      (node (ref "IC7") (pin "1") (pinfunction "GND_1") (pintype "power_in"))
      (node (ref "IC8") (pin "11") (pinfunction "HPGND_11") (pintype "bidirectional"))
      (node (ref "IC8") (pin "15") (pinfunction "AGND_15") (pintype "bidirectional"))
      (node (ref "IC8") (pin "21") (pinfunction "MODE_21") (pintype "bidirectional"))
      (node (ref "IC8") (pin "22") (pinfunction "CSB_22") (pintype "bidirectional"))
      (node (ref "IC8") (pin "28") (pinfunction "DGND_28") (pintype "bidirectional"))
      (node (ref "IC9") (pin "3") (pinfunction "+IN_3") (pintype "input"))
      (node (ref "IC9") (pin "5") (pinfunction "+IN_5") (pintype "input"))
      (node (ref "J1") (pin "P1") (pinfunction "1_P1") (pintype "passive"))
      (node (ref "J1") (pin "P2") (pinfunction "2_P2") (pintype "passive"))
      (node (ref "J10") (pin "P1") (pinfunction "1_P1") (pintype "passive"))
      (node (ref "J11") (pin "P1") (pinfunction "1_P1") (pintype "passive"))
      (node (ref "J12") (pin "P1") (pinfunction "1_P1") (pintype "passive"))
      (node (ref "J2") (pin "P1") (pinfunction "1_P1") (pintype "passive"))
      (node (ref "J2") (pin "P2") (pinfunction "2_P2") (pintype "passive"))
      (node (ref "J3") (pin "P1") (pinfunction "1_P1") (pintype "passive"))
      (node (ref "J4") (pin "P1") (pinfunction "1_P1") (pintype "passive"))
      (node (ref "J5") (pin "P1") (pinfunction "1_P1") (pintype "passive"))
      (node (ref "J6") (pin "P1") (pinfunction "1_P1") (pintype "passive"))
      (node (ref "J7") (pin "P1") (pinfunction "1_P1") (pintype "passive"))
      (node (ref "J8") (pin "P1") (pinfunction "1_P1") (pintype "passive"))
      (node (ref "J9") (pin "P1") (pinfunction "1_P1") (pintype "passive"))
      (node (ref "JP1") (pin "1") (pinfunction "1_1") (pintype "passive"))
      (node (ref "JP2") (pin "3") (pinfunction "3_3") (pintype "passive"))
      (node (ref "JP2") (pin "5") (pinfunction "5_5") (pintype "passive"))
      (node (ref "JP2") (pin "9") (pinfunction "9_9") (pintype "passive"))
      (node (ref "JP3") (pin "3") (pinfunction "3_3") (pintype "passive"))
      (node (ref "JP3") (pin "4") (pinfunction "4_4") (pintype "passive"))
      (node (ref "JP3") (pin "5") (pinfunction "5_5") (pintype "passive"))
      (node (ref "JP3") (pin "6") (pinfunction "6_6") (pintype "passive"))
      (node (ref "JP3") (pin "7") (pinfunction "7_7") (pintype "passive"))
      (node (ref "JP3") (pin "8") (pinfunction "8_8") (pintype "passive"))
      (node (ref "LED1") (pin "2") (pinfunction "C_2") (pintype "bidirectional"))
      (node (ref "LED2") (pin "2") (pinfunction "C_2") (pintype "bidirectional"))
      (node (ref "LED3") (pin "2") (pinfunction "C_2") (pintype "bidirectional"))
      (node (ref "LED4") (pin "2") (pinfunction "C_2") (pintype "bidirectional"))
      (node (ref "Q1") (pin "E") (pinfunction "E_E") (pintype "passive"))
      (node (ref "Q2") (pin "E") (pinfunction "E_E") (pintype "passive"))
      (node (ref "R13") (pin "1") (pinfunction "1_1") (pintype "passive"))
      (node (ref "R18") (pin "P$1") (pinfunction "E_P$1") (pintype "passive"))
      (node (ref "R19") (pin "P$3") (pinfunction "A_P$3") (pintype "passive"))
      (node (ref "R20") (pin "P$3") (pinfunction "A_P$3") (pintype "passive"))
      (node (ref "R43") (pin "P$1") (pinfunction "E_P$1") (pintype "passive"))
      (node (ref "R44") (pin "P$3") (pinfunction "A_P$3") (pintype "passive"))
      (node (ref "R45") (pin "P$3") (pinfunction "A_P$3") (pintype "passive"))
      (node (ref "R50") (pin "1") (pinfunction "1_1") (pintype "passive"))
      (node (ref "R54") (pin "1") (pinfunction "1_1") (pintype "passive"))
      (node (ref "R56") (pin "1") (pinfunction "1_1") (pintype "passive"))
      (node (ref "R59") (pin "1") (pinfunction "1_1") (pintype "passive"))
      (node (ref "SW1") (pin "L2") (pinfunction "L2_L2") (pintype "passive"))
      (node (ref "SW1") (pin "P3") (pinfunction "A3_P3") (pintype "passive"))
      (node (ref "SW1") (pin "P6") (pinfunction "B3_P6") (pintype "passive"))
      (node (ref "SW2") (pin "1") (pinfunction "1_1") (pintype "passive"))
      (node (ref "SW2") (pin "2") (pinfunction "2_2") (pintype "passive"))
      (node (ref "SW3") (pin "1") (pinfunction "1_1") (pintype "passive"))
      (node (ref "SW3") (pin "2") (pinfunction "2_2") (pintype "passive"))
      (node (ref "SW5") (pin "A") (pinfunction "P_A") (pintype "passive"))
      (node (ref "SW5") (pin "A'") (pinfunction "P1_A'") (pintype "passive"))
    )
    (net (code "9") (name "I2C_SCL") (class "Default")
      (node (ref "IC5") (pin "29") (pinfunction "PB10/SPI2_SCK/I2S_SCK/I2C2_SCL/USART3_TX_29") (pintype "bidirectional"))
      (node (ref "IC8") (pin "24") (pinfunction "SCLK_24") (pintype "bidirectional"))
      (node (ref "R40") (pin "1") (pinfunction "1_1") (pintype "passive"))
    )
    (net (code "10") (name "I2C_SDA") (class "Default")
      (node (ref "IC5") (pin "30") (pinfunction "PB11/I2C2_SDA/USART3_RX_30") (pintype "bidirectional"))
      (node (ref "IC8") (pin "23") (pinfunction "SDIN_23") (pintype "bidirectional"))
      (node (ref "R41") (pin "1") (pinfunction "1_1") (pintype "passive"))
    )
    (net (code "11") (name "I2S_LRCK") (class "Default")
      (node (ref "IC5") (pin "33") (pinfunction "PB12/SPI2_NSS/I2S2_WS/I2C2_SMBA/USART3_CK/TIM1_BKIN_33") (pintype "bidirectional"))
      (node (ref "IC8") (pin "5") (pinfunction "DACLRC_5") (pintype "bidirectional"))
      (node (ref "IC8") (pin "7") (pinfunction "ADCLRC_7") (pintype "bidirectional"))
    )
    (net (code "12") (name "I2S_SCK") (class "Default")
      (node (ref "IC5") (pin "34") (pinfunction "PB13/SPI2_SCK/I2S2_SCK/USART3_CTS/TIM1_CH1N_34") (pintype "bidirectional"))
      (node (ref "IC8") (pin "3") (pinfunction "BCLK_3") (pintype "bidirectional"))
    )
    (net (code "13") (name "I2S_SIN") (class "Default")
      (node (ref "IC5") (pin "35") (pinfunction "PB14/SPI2_MISO/USART3_RTS/TIM1_CH2N_35") (pintype "bidirectional"))
      (node (ref "IC8") (pin "6") (pinfunction "ADCDAT_6") (pintype "bidirectional"))
    )
    (net (code "14") (name "I2S_SOUT") (class "Default")
      (node (ref "IC5") (pin "36") (pinfunction "PB15/SPI2_MOSI/I2S2_SD/TIM1_CH3N_36") (pintype "bidirectional"))
      (node (ref "IC8") (pin "4") (pinfunction "DACDAT_4") (pintype "bidirectional"))
    )
    (net (code "15") (name "JTCK") (class "Default")
      (node (ref "IC5") (pin "49") (pinfunction "PA14/JTCK-SWCLK_49") (pintype "bidirectional"))
      (node (ref "JP2") (pin "4") (pinfunction "4_4") (pintype "passive"))
    )
    (net (code "16") (name "JTDI") (class "Default")
      (node (ref "IC5") (pin "50") (pinfunction "PA15/JTDI/SPI3_NSS/I2S3_WS_50") (pintype "bidirectional"))
      (node (ref "JP2") (pin "8") (pinfunction "8_8") (pintype "passive"))
    )
    (net (code "17") (name "JTDO") (class "Default")
      (node (ref "IC5") (pin "55") (pinfunction "PB3/JTDO/SPI3_SCK/I2S3_SCK_55") (pintype "bidirectional"))
      (node (ref "JP2") (pin "6") (pinfunction "6_6") (pintype "passive"))
    )
    (net (code "18") (name "JTMS") (class "Default")
      (node (ref "IC5") (pin "46") (pinfunction "PA13/JTMS-SWDAT_46") (pintype "bidirectional"))
      (node (ref "JP2") (pin "2") (pinfunction "2_2") (pintype "passive"))
    )
    (net (code "19") (name "LED_DATA") (class "Default")
      (node (ref "IC1") (pin "14") (pinfunction "SER_14") (pintype "input"))
      (node (ref "IC5") (pin "57") (pinfunction "PB5/I2C1_SMBA/SPI1_MOSI/SPI3_MOSI/I2S3_SD_57") (pintype "bidirectional"))
    )
    (net (code "20") (name "LED_EN") (class "Default")
      (node (ref "IC1") (pin "12") (pinfunction "RCK_12") (pintype "input"))
      (node (ref "IC5") (pin "24") (pinfunction "PC4/ADC14_24") (pintype "bidirectional"))
    )
    (net (code "21") (name "LED_REC") (class "Default")
      (node (ref "IC5") (pin "62") (pinfunction "PB9/SPI2_NSS/I2S2_WS/I2C1_SDA/TIM4_CH4_62") (pintype "bidirectional"))
      (node (ref "R1") (pin "1") (pinfunction "1_1") (pintype "passive"))
      (node (ref "R2") (pin "1") (pinfunction "1_1") (pintype "passive"))
    )
    (net (code "22") (name "LED_SCK") (class "Default")
      (node (ref "IC1") (pin "11") (pinfunction "SCK_11") (pintype "input"))
      (node (ref "IC5") (pin "25") (pinfunction "PC5/ADC15_25") (pintype "bidirectional"))
    )
    (net (code "23") (name "LIN") (class "Default")
      (node (ref "C37") (pin "+") (pinfunction "+_+") (pintype "passive"))
      (node (ref "IC8") (pin "20") (pinfunction "LLINEIN_20") (pintype "bidirectional"))
    )
    (net (code "24") (name "LOUT") (class "Default")
      (node (ref "C33") (pin "+") (pinfunction "+_+") (pintype "passive"))
      (node (ref "IC8") (pin "12") (pinfunction "LOUT_12") (pintype "bidirectional"))
    )
    (net (code "25") (name "Net-(C33-Pad-)") (class "Default")
      (node (ref "C33") (pin "-") (pinfunction "-_-") (pintype "passive"))
      (node (ref "R51") (pin "2") (pinfunction "2_2") (pintype "passive"))
      (node (ref "R59") (pin "2") (pinfunction "2_2") (pintype "passive"))
    )
    (net (code "26") (name "Net-(C36-Pad-)") (class "Default")
      (node (ref "C36") (pin "-") (pinfunction "-_-") (pintype "passive"))
      (node (ref "C43") (pin "1") (pinfunction "1_1") (pintype "passive"))
      (node (ref "R53") (pin "1") (pinfunction "1_1") (pintype "passive"))
      (node (ref "R54") (pin "2") (pinfunction "2_2") (pintype "passive"))
    )
    (net (code "27") (name "Net-(C37-Pad-)") (class "Default")
      (node (ref "C37") (pin "-") (pinfunction "-_-") (pintype "passive"))
      (node (ref "C44") (pin "1") (pinfunction "1_1") (pintype "passive"))
      (node (ref "R55") (pin "1") (pinfunction "1_1") (pintype "passive"))
      (node (ref "R56") (pin "2") (pinfunction "2_2") (pintype "passive"))
    )
    (net (code "28") (name "Net-(C41-Pad-)") (class "Default")
      (node (ref "C41") (pin "-") (pinfunction "-_-") (pintype "passive"))
      (node (ref "R50") (pin "2") (pinfunction "2_2") (pintype "passive"))
      (node (ref "R52") (pin "2") (pinfunction "2_2") (pintype "passive"))
    )
    (net (code "29") (name "Net-(D1-PadA)") (class "Default")
      (node (ref "D1") (pin "A") (pinfunction "A_A") (pintype "passive"))
      (node (ref "JP3") (pin "1") (pinfunction "1_1") (pintype "passive"))
      (node (ref "JP3") (pin "2") (pinfunction "2_2") (pintype "passive"))
    )
    (net (code "30") (name "Net-(D2-PadC)") (class "Default")
      (node (ref "D2") (pin "C") (pinfunction "C_C") (pintype "passive"))
      (node (ref "JP3") (pin "10") (pinfunction "10_10") (pintype "passive"))
      (node (ref "JP3") (pin "9") (pinfunction "9_9") (pintype "passive"))
    )
    (net (code "31") (name "Net-(IC1A-QA)") (class "Default")
      (node (ref "IC1") (pin "15") (pinfunction "QA_15") (pintype "tri_state"))
      (node (ref "R10") (pin "2") (pinfunction "2_2") (pintype "passive"))
    )
    (net (code "32") (name "Net-(IC1A-QB)") (class "Default")
      (node (ref "IC1") (pin "1") (pinfunction "QB_1") (pintype "tri_state"))
      (node (ref "R9") (pin "2") (pinfunction "2_2") (pintype "passive"))
    )
    (net (code "33") (name "Net-(IC1A-QC)") (class "Default")
      (node (ref "IC1") (pin "2") (pinfunction "QC_2") (pintype "tri_state"))
      (node (ref "R8") (pin "2") (pinfunction "2_2") (pintype "passive"))
    )
    (net (code "34") (name "Net-(IC1A-QD)") (class "Default")
      (node (ref "IC1") (pin "3") (pinfunction "QD_3") (pintype "tri_state"))
      (node (ref "R7") (pin "2") (pinfunction "2_2") (pintype "passive"))
    )
    (net (code "35") (name "Net-(IC1A-QE)") (class "Default")
      (node (ref "IC1") (pin "4") (pinfunction "QE_4") (pintype "tri_state"))
      (node (ref "R6") (pin "2") (pinfunction "2_2") (pintype "passive"))
    )
    (net (code "36") (name "Net-(IC1A-QF)") (class "Default")
      (node (ref "IC1") (pin "5") (pinfunction "QF_5") (pintype "tri_state"))
      (node (ref "R5") (pin "2") (pinfunction "2_2") (pintype "passive"))
    )
    (net (code "37") (name "Net-(IC1A-QG)") (class "Default")
      (node (ref "IC1") (pin "6") (pinfunction "QG_6") (pintype "tri_state"))
      (node (ref "R3") (pin "2") (pinfunction "2_2") (pintype "passive"))
    )
    (net (code "38") (name "Net-(IC1A-QH)") (class "Default")
      (node (ref "IC1") (pin "7") (pinfunction "QH_7") (pintype "tri_state"))
      (node (ref "R4") (pin "2") (pinfunction "2_2") (pintype "passive"))
    )
    (net (code "39") (name "Net-(IC2-VIN)") (class "Default")
      (node (ref "C2") (pin "+") (pinfunction "+_+") (pintype "passive"))
      (node (ref "IC2") (pin "2") (pinfunction "VIN_2") (pintype "input"))
      (node (ref "R11") (pin "2") (pinfunction "2_2") (pintype "passive"))
    )
    (net (code "40") (name "Net-(IC3A--IN)") (class "Default")
      (node (ref "C22") (pin "1") (pinfunction "1_1") (pintype "passive"))
      (node (ref "IC3") (pin "2") (pinfunction "-IN_2") (pintype "input"))
      (node (ref "R31") (pin "2") (pinfunction "2_2") (pintype "passive"))
      (node (ref "R32") (pin "1") (pinfunction "1_1") (pintype "passive"))
      (node (ref "R33") (pin "1") (pinfunction "1_1") (pintype "passive"))
    )
    (net (code "41") (name "Net-(IC3B--IN)") (class "Default")
      (node (ref "C9") (pin "1") (pinfunction "1_1") (pintype "passive"))
      (node (ref "IC3") (pin "6") (pinfunction "-IN_6") (pintype "input"))
      (node (ref "R27") (pin "2") (pinfunction "2_2") (pintype "passive"))
      (node (ref "R28") (pin "1") (pinfunction "1_1") (pintype "passive"))
      (node (ref "R29") (pin "1") (pinfunction "1_1") (pintype "passive"))
    )
    (net (code "42") (name "Net-(IC4A--IN)") (class "Default")
      (node (ref "C20") (pin "1") (pinfunction "1_1") (pintype "passive"))
      (node (ref "IC4") (pin "2") (pinfunction "-IN_2") (pintype "input"))
      (node (ref "R34") (pin "2") (pinfunction "2_2") (pintype "passive"))
      (node (ref "R36") (pin "1") (pinfunction "1_1") (pintype "passive"))
      (node (ref "R38") (pin "1") (pinfunction "1_1") (pintype "passive"))
    )
    (net (code "43") (name "Net-(IC4B--IN)") (class "Default")
      (node (ref "C21") (pin "1") (pinfunction "1_1") (pintype "passive"))
      (node (ref "IC4") (pin "6") (pinfunction "-IN_6") (pintype "input"))
      (node (ref "R35") (pin "2") (pinfunction "2_2") (pintype "passive"))
      (node (ref "R37") (pin "1") (pinfunction "1_1") (pintype "passive"))
      (node (ref "R39") (pin "1") (pinfunction "1_1") (pintype "passive"))
    )
    (net (code "44") (name "Net-(IC4C--IN)") (class "Default")
      (node (ref "C11") (pin "1") (pinfunction "1_1") (pintype "passive"))
      (node (ref "IC4") (pin "9") (pinfunction "-IN_9") (pintype "input"))
      (node (ref "R23") (pin "1") (pinfunction "1_1") (pintype "passive"))
      (node (ref "R24") (pin "1") (pinfunction "1_1") (pintype "passive"))
      (node (ref "R26") (pin "2") (pinfunction "2_2") (pintype "passive"))
    )
    (net (code "45") (name "Net-(IC4D--IN)") (class "Default")
      (node (ref "C10") (pin "1") (pinfunction "1_1") (pintype "passive"))
      (node (ref "IC4") (pin "13") (pinfunction "-IN_13") (pintype "input"))
      (node (ref "R21") (pin "1") (pinfunction "1_1") (pintype "passive"))
      (node (ref "R22") (pin "1") (pinfunction "1_1") (pintype "passive"))
      (node (ref "R25") (pin "2") (pinfunction "2_2") (pintype "passive"))
    )
    (net (code "46") (name "Net-(IC5-PD0{slash}OSC_IN)") (class "Default")
      (node (ref "C7") (pin "2") (pinfunction "2_2") (pintype "passive"))
      (node (ref "IC5") (pin "5") (pinfunction "PD0/OSC_IN_5") (pintype "bidirectional"))
      (node (ref "Q3") (pin "2") (pinfunction "2_2") (pintype "passive"))
    )
    (net (code "47") (name "Net-(IC5-PD1{slash}OSC_OUT)") (class "Default")
      (node (ref "C6") (pin "2") (pinfunction "2_2") (pintype "passive"))
      (node (ref "IC5") (pin "6") (pinfunction "PD1/OSC_OUT_6") (pintype "bidirectional"))
      (node (ref "Q3") (pin "1") (pinfunction "1_1") (pintype "passive"))
    )
    (net (code "48") (name "Net-(IC5-VCAP_1)") (class "Default")
      (node (ref "C24") (pin "1") (pinfunction "1_1") (pintype "passive"))
      (node (ref "IC5") (pin "31") (pinfunction "VCAP_1_31") (pintype "power_in"))
    )
    (net (code "49") (name "Net-(IC5-VCAP_2)") (class "Default")
      (node (ref "C19") (pin "1") (pinfunction "1_1") (pintype "passive"))
      (node (ref "IC5") (pin "47") (pinfunction "VCAP_2_47") (pintype "power_in"))
    )
    (net (code "50") (name "Net-(IC8-VMID)") (class "Default")
      (node (ref "C34") (pin "1") (pinfunction "1_1") (pintype "passive"))
      (node (ref "C35") (pin "+") (pinfunction "+_+") (pintype "passive"))
      (node (ref "IC8") (pin "16") (pinfunction "VMID_16") (pintype "bidirectional"))
    )
    (net (code "51") (name "Net-(IC8-XTI{slash}MCLK)") (class "Default")
      (node (ref "C48") (pin "2") (pinfunction "2_2") (pintype "passive"))
      (node (ref "IC8") (pin "25") (pinfunction "XTI/MCLK_25") (pintype "bidirectional"))
      (node (ref "Q4") (pin "2") (pinfunction "2_2") (pintype "passive"))
    )
    (net (code "52") (name "Net-(IC8-XTO)") (class "Default")
      (node (ref "C47") (pin "2") (pinfunction "2_2") (pintype "passive"))
      (node (ref "IC8") (pin "26") (pinfunction "XTO_26") (pintype "bidirectional"))
      (node (ref "Q4") (pin "1") (pinfunction "1_1") (pintype "passive"))
    )
    (net (code "53") (name "Net-(IC9A--IN)") (class "Default")
      (node (ref "IC9") (pin "2") (pinfunction "-IN_2") (pintype "input"))
      (node (ref "R46") (pin "2") (pinfunction "2_2") (pintype "passive"))
      (node (ref "R57") (pin "1") (pinfunction "1_1") (pintype "passive"))
    )
    (net (code "54") (name "Net-(IC9A-OUT)") (class "Default")
      (node (ref "IC9") (pin "1") (pinfunction "OUT_1") (pintype "output"))
      (node (ref "R42") (pin "2-2") (pinfunction "S_2-2") (pintype "passive"))
      (node (ref "R42") (pin "2-3") (pinfunction "E_2-3") (pintype "passive"))
      (node (ref "R55") (pin "2") (pinfunction "2_2") (pintype "passive"))
    )
    (net (code "55") (name "Net-(IC9B--IN)") (class "Default")
      (node (ref "IC9") (pin "6") (pinfunction "-IN_6") (pintype "input"))
      (node (ref "R47") (pin "2") (pinfunction "2_2") (pintype "passive"))
      (node (ref "R58") (pin "1") (pinfunction "1_1") (pintype "passive"))
    )
    (net (code "56") (name "Net-(IC9B-OUT)") (class "Default")
      (node (ref "IC9") (pin "7") (pinfunction "OUT_7") (pintype "output"))
      (node (ref "R42") (pin "1-2") (pinfunction "S_1-2") (pintype "passive"))
      (node (ref "R42") (pin "1-3") (pinfunction "E_1-3") (pintype "passive"))
      (node (ref "R53") (pin "2") (pinfunction "2_2") (pintype "passive"))
    )
    (net (code "57") (name "Net-(IC10A--IN)") (class "Default")
      (node (ref "C40") (pin "1") (pinfunction "1_1") (pintype "passive"))
      (node (ref "IC10") (pin "2") (pinfunction "-IN_2") (pintype "input"))
      (node (ref "R49") (pin "2") (pinfunction "2_2") (pintype "passive"))
      (node (ref "R51") (pin "1") (pinfunction "1_1") (pintype "passive"))
    )
    (net (code "58") (name "Net-(IC10A-OUT)") (class "Default")
      (node (ref "C40") (pin "2") (pinfunction "2_2") (pintype "passive"))
      (node (ref "IC10") (pin "1") (pinfunction "OUT_1") (pintype "output"))
      (node (ref "R49") (pin "1") (pinfunction "1_1") (pintype "passive"))
      (node (ref "R61") (pin "2") (pinfunction "2_2") (pintype "passive"))
    )
    (net (code "59") (name "Net-(IC10B--IN)") (class "Default")
      (node (ref "C42") (pin "1") (pinfunction "1_1") (pintype "passive"))
      (node (ref "IC10") (pin "6") (pinfunction "-IN_6") (pintype "input"))
      (node (ref "R48") (pin "2") (pinfunction "2_2") (pintype "passive"))
      (node (ref "R52") (pin "1") (pinfunction "1_1") (pintype "passive"))
    )
    (net (code "60") (name "Net-(IC10B-OUT)") (class "Default")
      (node (ref "C42") (pin "2") (pinfunction "2_2") (pintype "passive"))
      (node (ref "IC10") (pin "7") (pinfunction "OUT_7") (pintype "output"))
      (node (ref "R48") (pin "1") (pinfunction "1_1") (pintype "passive"))
      (node (ref "R62") (pin "2") (pinfunction "2_2") (pintype "passive"))
    )
    (net (code "61") (name "Net-(J1-3)") (class "Default")
      (node (ref "J1") (pin "P3") (pinfunction "3_P3") (pintype "passive"))
      (node (ref "R12") (pin "1") (pinfunction "1_1") (pintype "passive"))
    )
    (net (code "62") (name "Net-(J2-3)") (class "Default")
      (node (ref "J2") (pin "P3") (pinfunction "3_P3") (pintype "passive"))
      (node (ref "R15") (pin "1") (pinfunction "1_1") (pintype "passive"))
    )
    (net (code "63") (name "Net-(J3-3)") (class "Default")
      (node (ref "J3") (pin "P3") (pinfunction "3_P3") (pintype "passive"))
      (node (ref "R29") (pin "2") (pinfunction "2_2") (pintype "passive"))
    )
    (net (code "64") (name "Net-(J4-3)") (class "Default")
      (node (ref "J4") (pin "P3") (pinfunction "3_P3") (pintype "passive"))
      (node (ref "R21") (pin "2") (pinfunction "2_2") (pintype "passive"))
    )
    (net (code "65") (name "Net-(J5-3)") (class "Default")
      (node (ref "J5") (pin "P3") (pinfunction "3_P3") (pintype "passive"))
      (node (ref "R38") (pin "2") (pinfunction "2_2") (pintype "passive"))
    )
    (net (code "66") (name "Net-(J6-3)") (class "Default")
      (node (ref "J6") (pin "P3") (pinfunction "3_P3") (pintype "passive"))
      (node (ref "R39") (pin "2") (pinfunction "2_2") (pintype "passive"))
    )
    (net (code "67") (name "Net-(J7-3)") (class "Default")
      (node (ref "J7") (pin "P3") (pinfunction "3_P3") (pintype "passive"))
      (node (ref "J8") (pin "P2") (pinfunction "2_P2") (pintype "passive"))
      (node (ref "R57") (pin "2") (pinfunction "2_2") (pintype "passive"))
    )
    (net (code "68") (name "Net-(J8-3)") (class "Default")
      (node (ref "J8") (pin "P3") (pinfunction "3_P3") (pintype "passive"))
      (node (ref "R58") (pin "2") (pinfunction "2_2") (pintype "passive"))
    )
    (net (code "69") (name "Net-(J9-3)") (class "Default")
      (node (ref "J9") (pin "P3") (pinfunction "3_P3") (pintype "passive"))
      (node (ref "R32") (pin "2") (pinfunction "2_2") (pintype "passive"))
    )
    (net (code "70") (name "Net-(J10-3)") (class "Default")
      (node (ref "J10") (pin "P3") (pinfunction "3_P3") (pintype "passive"))
      (node (ref "R24") (pin "2") (pinfunction "2_2") (pintype "passive"))
    )
    (net (code "71") (name "Net-(J11-3)") (class "Default")
      (node (ref "J11") (pin "P3") (pinfunction "3_P3") (pintype "passive"))
      (node (ref "R61") (pin "1") (pinfunction "1_1") (pintype "passive"))
    )
    (net (code "72") (name "Net-(J12-3)") (class "Default")
      (node (ref "J12") (pin "P3") (pinfunction "3_P3") (pintype "passive"))
      (node (ref "R62") (pin "1") (pinfunction "1_1") (pintype "passive"))
    )
    (net (code "73") (name "Net-(LED1-GRN)") (class "Default")
      (node (ref "LED1") (pin "3") (pinfunction "GRN_3") (pintype "bidirectional"))
      (node (ref "R4") (pin "1") (pinfunction "1_1") (pintype "passive"))
    )
    (net (code "74") (name "Net-(LED1-RED)") (class "Default")
      (node (ref "LED1") (pin "1") (pinfunction "RED_1") (pintype "bidirectional"))
      (node (ref "R3") (pin "1") (pinfunction "1_1") (pintype "passive"))
    )
    (net (code "75") (name "Net-(LED2-GRN)") (class "Default")
      (node (ref "LED2") (pin "3") (pinfunction "GRN_3") (pintype "bidirectional"))
      (node (ref "R5") (pin "1") (pinfunction "1_1") (pintype "passive"))
    )
    (net (code "76") (name "Net-(LED2-RED)") (class "Default")
      (node (ref "LED2") (pin "1") (pinfunction "RED_1") (pintype "bidirectional"))
      (node (ref "R6") (pin "1") (pinfunction "1_1") (pintype "passive"))
    )
    (net (code "77") (name "Net-(LED3-GRN)") (class "Default")
      (node (ref "LED3") (pin "3") (pinfunction "GRN_3") (pintype "bidirectional"))
      (node (ref "R7") (pin "1") (pinfunction "1_1") (pintype "passive"))
    )
    (net (code "78") (name "Net-(LED3-RED)") (class "Default")
      (node (ref "LED3") (pin "1") (pinfunction "RED_1") (pintype "bidirectional"))
      (node (ref "R8") (pin "1") (pinfunction "1_1") (pintype "passive"))
    )
    (net (code "79") (name "Net-(LED4-GRN)") (class "Default")
      (node (ref "LED4") (pin "3") (pinfunction "GRN_3") (pintype "bidirectional"))
      (node (ref "R9") (pin "1") (pinfunction "1_1") (pintype "passive"))
    )
    (net (code "80") (name "Net-(LED4-RED)") (class "Default")
      (node (ref "LED4") (pin "1") (pinfunction "RED_1") (pintype "bidirectional"))
      (node (ref "R10") (pin "1") (pinfunction "1_1") (pintype "passive"))
    )
    (net (code "81") (name "Net-(Q1-PadB)") (class "Default")
      (node (ref "Q1") (pin "B") (pinfunction "B_B") (pintype "passive"))
      (node (ref "R12") (pin "2") (pinfunction "2_2") (pintype "passive"))
    )
    (net (code "82") (name "Net-(Q2-PadB)") (class "Default")
      (node (ref "Q2") (pin "B") (pinfunction "B_B") (pintype "passive"))
      (node (ref "R15") (pin "2") (pinfunction "2_2") (pintype "passive"))
    )
    (net (code "83") (name "Net-(R1-Pad2)") (class "Default")
      (node (ref "R1") (pin "2") (pinfunction "2_2") (pintype "passive"))
      (node (ref "R2") (pin "2") (pinfunction "2_2") (pintype "passive"))
      (node (ref "SW1") (pin "L1") (pinfunction "L1_L1") (pintype "passive"))
    )
    (net (code "84") (name "Net-(R18-S)") (class "Default")
      (node (ref "R18") (pin "P$2") (pinfunction "S_P$2") (pintype "passive"))
      (node (ref "R28") (pin "2") (pinfunction "2_2") (pintype "passive"))
    )
    (net (code "85") (name "Net-(R42A-A)") (class "Default")
      (node (ref "R42") (pin "1-1") (pinfunction "A_1-1") (pintype "passive"))
      (node (ref "R47") (pin "1") (pinfunction "1_1") (pintype "passive"))
    )
    (net (code "86") (name "Net-(R42B-A)") (class "Default")
      (node (ref "R42") (pin "2-1") (pinfunction "A_2-1") (pintype "passive"))
      (node (ref "R46") (pin "1") (pinfunction "1_1") (pintype "passive"))
    )
    (net (code "87") (name "Net-(R43-S)") (class "Default")
      (node (ref "R33") (pin "2") (pinfunction "2_2") (pintype "passive"))
      (node (ref "R43") (pin "P$2") (pinfunction "S_P$2") (pintype "passive"))
    )
    (net (code "88") (name "PITCH_POT") (class "Default")
      (node (ref "IC5") (pin "9") (pinfunction "PC1/ADC11_9") (pintype "bidirectional"))
      (node (ref "R20") (pin "P$2") (pinfunction "S_P$2") (pintype "passive"))
    )
    (net (code "89") (name "PLAY") (class "Default")
      (node (ref "IC5") (pin "58") (pinfunction "PB6/I2C1_SCL/TIM4_CH1/USART1_TX_58") (pintype "bidirectional"))
      (node (ref "Q2") (pin "C") (pinfunction "C_C") (pintype "passive"))
      (node (ref "R16") (pin "1") (pinfunction "1_1") (pintype "passive"))
    )
    (net (code "90") (name "POSITION_POT_CV") (class "Default")
      (node (ref "C9") (pin "2") (pinfunction "2_2") (pintype "passive"))
      (node (ref "IC3") (pin "7") (pinfunction "OUT_7") (pintype "output"))
      (node (ref "IC5") (pin "16") (pinfunction "PA2/USART2_TX/ADC2/TIM2_CH3_16") (pintype "bidirectional"))
      (node (ref "R27") (pin "1") (pinfunction "1_1") (pintype "passive"))
    )
    (net (code "91") (name "REC") (class "Default")
      (node (ref "IC5") (pin "59") (pinfunction "PB7/I2C1_SDA/TIM4_CH2/USART1_RX_59") (pintype "bidirectional"))
      (node (ref "Q1") (pin "C") (pinfunction "C_C") (pintype "passive"))
      (node (ref "R14") (pin "1") (pinfunction "1_1") (pintype "passive"))
    )
    (net (code "92") (name "RESET") (class "Default")
      (node (ref "IC5") (pin "7") (pinfunction "NRST_7") (pintype "bidirectional"))
      (node (ref "JP2") (pin "10") (pinfunction "10_10") (pintype "passive"))
      (node (ref "R17") (pin "1") (pinfunction "1_1") (pintype "passive"))
      (node (ref "SW5") (pin "B") (pinfunction "S_B") (pintype "passive"))
      (node (ref "SW5") (pin "B'") (pinfunction "S1_B'") (pintype "passive"))
    )
    (net (code "93") (name "RIN") (class "Default")
      (node (ref "C36") (pin "+") (pinfunction "+_+") (pintype "passive"))
      (node (ref "IC8") (pin "19") (pinfunction "RLINEIN_19") (pintype "bidirectional"))
    )
    (net (code "94") (name "ROUT") (class "Default")
      (node (ref "C41") (pin "+") (pinfunction "+_+") (pintype "passive"))
      (node (ref "IC8") (pin "13") (pinfunction "ROUT_13") (pintype "bidirectional"))
    )
    (net (code "95") (name "RX") (class "Default")
      (node (ref "IC5") (pin "43") (pinfunction "PA10/USART1_RX/TIM1_CH3_43") (pintype "bidirectional"))
      (node (ref "JP1") (pin "4") (pinfunction "4_4") (pintype "passive"))
    )
    (net (code "96") (name "SIZE_CV") (class "Default")
      (node (ref "C10") (pin "2") (pinfunction "2_2") (pintype "passive"))
      (node (ref "IC4") (pin "14") (pinfunction "OUT_14") (pintype "output"))
      (node (ref "IC5") (pin "15") (pinfunction "PA1/USART2_RTS/UART4_RX/ADC1/TIM2_CH2_15") (pintype "bidirectional"))
      (node (ref "R25") (pin "1") (pinfunction "1_1") (pintype "passive"))
    )
    (net (code "97") (name "SIZE_POT") (class "Default")
      (node (ref "IC5") (pin "8") (pinfunction "PC0/ADC10_8") (pintype "bidirectional"))
      (node (ref "R19") (pin "P$2") (pinfunction "S_P$2") (pintype "passive"))
    )
    (net (code "98") (name "SW_LOAD") (class "Default")
      (node (ref "IC5") (pin "51") (pinfunction "PC10/SPI3_SCK/I2S3_SCK/UART4_TX_51") (pintype "bidirectional"))
      (node (ref "SW3") (pin "3") (pinfunction "3_3") (pintype "passive"))
      (node (ref "SW3") (pin "4") (pinfunction "4_4") (pintype "passive"))
    )
    (net (code "99") (name "SW_MODE") (class "Default")
      (node (ref "IC5") (pin "52") (pinfunction "PC11/UART4_RX/SPI3_MISO/USART3_RX_52") (pintype "bidirectional"))
      (node (ref "SW2") (pin "3") (pinfunction "3_3") (pintype "passive"))
      (node (ref "SW2") (pin "4") (pinfunction "4_4") (pintype "passive"))
    )
    (net (code "100") (name "SW_REC") (class "Default")
      (node (ref "IC5") (pin "61") (pinfunction "PB8/TIM4_CH3/I2C1_SCL_61") (pintype "bidirectional"))
      (node (ref "SW1") (pin "P2") (pinfunction "A2_P2") (pintype "passive"))
      (node (ref "SW1") (pin "P5") (pinfunction "B2_P5") (pintype "passive"))
    )
    (net (code "101") (name "TEXTURE_CV") (class "Default")
      (node (ref "C11") (pin "2") (pinfunction "2_2") (pintype "passive"))
      (node (ref "IC4") (pin "8") (pinfunction "OUT_8") (pintype "output"))
      (node (ref "IC5") (pin "14") (pinfunction "PA0-WKUP/USART2_CTS/UART4_TX/ADC0/TIM2_CH1_ETR_14") (pintype "bidirectional"))
      (node (ref "R26") (pin "1") (pinfunction "1_1") (pintype "passive"))
    )
    (net (code "102") (name "TEXTURE_POT") (class "Default")
      (node (ref "IC5") (pin "22") (pinfunction "PA6/SPI1_MISO/ADC6/TIM3_CH1_22") (pintype "bidirectional"))
      (node (ref "R44") (pin "P$2") (pinfunction "S_P$2") (pintype "passive"))
    )
    (net (code "103") (name "TX") (class "Default")
      (node (ref "IC5") (pin "42") (pinfunction "PA9/USART1_TX/TIM1_CH2_42") (pintype "bidirectional"))
      (node (ref "JP1") (pin "5") (pinfunction "5_5") (pintype "passive"))
    )
    (net (code "104") (name "VBAT") (class "Default")
      (node (ref "IC5") (pin "1") (pinfunction "VBAT_1") (pintype "power_in"))
    )
    (net (code "105") (name "VCC") (class "Default")
      (node (ref "C1") (pin "+") (pinfunction "+_+") (pintype "passive"))
      (node (ref "C38") (pin "1") (pinfunction "1_1") (pintype "passive"))
      (node (ref "C39") (pin "1") (pinfunction "1_1") (pintype "passive"))
      (node (ref "D1") (pin "C") (pinfunction "C_C") (pintype "passive"))
      (node (ref "IC10") (pin "8") (pinfunction "V+_8") (pintype "power_in"))
      (node (ref "IC7") (pin "3") (pinfunction "VIN_3") (pintype "input"))
      (node (ref "IC9") (pin "8") (pinfunction "V+_8") (pintype "power_in"))
      (node (ref "R11") (pin "1") (pinfunction "1_1") (pintype "passive"))
    )
    (net (code "106") (name "VEE") (class "Default")
      (node (ref "C13") (pin "-") (pinfunction "-_-") (pintype "passive"))
      (node (ref "C45") (pin "2") (pinfunction "2_2") (pintype "passive"))
      (node (ref "C46") (pin "2") (pinfunction "2_2") (pintype "passive"))
      (node (ref "D2") (pin "A") (pinfunction "A_A") (pintype "passive"))
      (node (ref "IC10") (pin "4") (pinfunction "V-_4") (pintype "power_in"))
      (node (ref "IC9") (pin "4") (pinfunction "V-_4") (pintype "power_in"))
      (node (ref "R30") (pin "1") (pinfunction "1_1") (pintype "passive"))
    )
    (net (code "107") (name "V_OCT") (class "Default")
      (node (ref "C20") (pin "2") (pinfunction "2_2") (pintype "passive"))
      (node (ref "IC4") (pin "1") (pinfunction "OUT_1") (pintype "output"))
      (node (ref "IC5") (pin "20") (pinfunction "PA4/SPI1_NSS/SPI3_NSS/USART2_CK/I2S3_WS/ADC4/DAC1_20") (pintype "bidirectional"))
      (node (ref "R34") (pin "1") (pinfunction "1_1") (pintype "passive"))
    )
    (net (code "108") (name "unconnected-(IC1A-QH*-Pad9)") (class "Default")
      (node (ref "IC1") (pin "9") (pinfunction "QH*_9") (pintype "tri_state"))
    )
    (net (code "109") (name "unconnected-(IC5-PA8{slash}USART1_CK{slash}TIM1_CH1{slash}MCO-Pad41)") (class "Default")
      (node (ref "IC5") (pin "41") (pinfunction "PA8/USART1_CK/TIM1_CH1/MCO_41") (pintype "bidirectional"))
    )
    (net (code "110") (name "unconnected-(IC5-PA11{slash}USART1_CTS{slash}CANRX{slash}USBDM{slash}TIM1_CH4-Pad44)") (class "Default")
      (node (ref "IC5") (pin "44") (pinfunction "PA11/USART1_CTS/CANRX/USBDM/TIM1_CH4_44") (pintype "bidirectional"))
    )
    (net (code "111") (name "unconnected-(IC5-PA12{slash}USART1_RTS{slash}CANTX{slash}USBDP{slash}TIM1_ETR-Pad45)") (class "Default")
      (node (ref "IC5") (pin "45") (pinfunction "PA12/USART1_RTS/CANTX/USBDP/TIM1_ETR_45") (pintype "bidirectional"))
    )
    (net (code "112") (name "unconnected-(IC5-PB1{slash}ADC9{slash}TIM3_CH4-Pad27)") (class "Default")
      (node (ref "IC5") (pin "27") (pinfunction "PB1/ADC9/TIM3_CH4_27") (pintype "bidirectional"))
    )
    (net (code "113") (name "unconnected-(IC5-PB4{slash}NJTRST{slash}SPI3_MISO{slash}SPI1_MISO-Pad56)") (class "Default")
      (node (ref "IC5") (pin "56") (pinfunction "PB4/NJTRST/SPI3_MISO/SPI1_MISO_56") (pintype "bidirectional"))
    )
    (net (code "114") (name "unconnected-(IC5-PC2{slash}SPI2_MISO{slash}ADC12-Pad10)") (class "Default")
      (node (ref "IC5") (pin "10") (pinfunction "PC2/SPI2_MISO/ADC12_10") (pintype "bidirectional"))
    )
    (net (code "115") (name "unconnected-(IC5-PC3{slash}SPI2_MOSI{slash}I2S2_SD{slash}ADC13-Pad11)") (class "Default")
      (node (ref "IC5") (pin "11") (pinfunction "PC3/SPI2_MOSI/I2S2_SD/ADC13_11") (pintype "bidirectional"))
    )
    (net (code "116") (name "unconnected-(IC5-PC6{slash}I2S2_MCK-Pad37)") (class "Default")
      (node (ref "IC5") (pin "37") (pinfunction "PC6/I2S2_MCK_37") (pintype "bidirectional"))
    )
    (net (code "117") (name "unconnected-(IC5-PC7{slash}I2S3_MCK-Pad38)") (class "Default")
      (node (ref "IC5") (pin "38") (pinfunction "PC7/I2S3_MCK_38") (pintype "bidirectional"))
    )
    (net (code "118") (name "unconnected-(IC5-PC8-Pad39)") (class "Default")
      (node (ref "IC5") (pin "39") (pinfunction "PC8_39") (pintype "bidirectional"))
    )
    (net (code "119") (name "unconnected-(IC5-PC9{slash}I2S2_CKIN{slash}I2S3_CKIN-Pad40)") (class "Default")
      (node (ref "IC5") (pin "40") (pinfunction "PC9/I2S2_CKIN/I2S3_CKIN_40") (pintype "bidirectional"))
    )
    (net (code "120") (name "unconnected-(IC5-PC12{slash}UART5_TX{slash}I2S3_SD{slash}USART3_CK-Pad53)") (class "Default")
      (node (ref "IC5") (pin "53") (pinfunction "PC12/UART5_TX/I2S3_SD/USART3_CK_53") (pintype "bidirectional"))
    )
    (net (code "121") (name "unconnected-(IC5-PC13-TAMPER-RTC-Pad2)") (class "Default")
      (node (ref "IC5") (pin "2") (pinfunction "PC13-TAMPER-RTC_2") (pintype "bidirectional"))
    )
    (net (code "122") (name "unconnected-(IC5-PC14{slash}OSC32_IN-Pad3)") (class "Default")
      (node (ref "IC5") (pin "3") (pinfunction "PC14/OSC32_IN_3") (pintype "bidirectional"))
    )
    (net (code "123") (name "unconnected-(IC5-PC15{slash}OSC_OUT-Pad4)") (class "Default")
      (node (ref "IC5") (pin "4") (pinfunction "PC15/OSC_OUT_4") (pintype "bidirectional"))
    )
    (net (code "124") (name "unconnected-(IC5-PD2{slash}TIM3-ETR-Pad54)") (class "Default")
      (node (ref "IC5") (pin "54") (pinfunction "PD2/TIM3-ETR_54") (pintype "bidirectional"))
    )
    (net (code "125") (name "unconnected-(IC8-CLKOUT-Pad2)") (class "Default")
      (node (ref "IC8") (pin "2") (pinfunction "CLKOUT_2") (pintype "bidirectional"))
    )
    (net (code "126") (name "unconnected-(IC8-LHPOUT-Pad9)") (class "Default")
      (node (ref "IC8") (pin "9") (pinfunction "LHPOUT_9") (pintype "bidirectional"))
    )
    (net (code "127") (name "unconnected-(IC8-MICBIAS-Pad17)") (class "Default")
      (node (ref "IC8") (pin "17") (pinfunction "MICBIAS_17") (pintype "bidirectional"))
    )
    (net (code "128") (name "unconnected-(IC8-MICIN-Pad18)") (class "Default")
      (node (ref "IC8") (pin "18") (pinfunction "MICIN_18") (pintype "bidirectional"))
    )
    (net (code "129") (name "unconnected-(IC8-RHPOUT-Pad10)") (class "Default")
      (node (ref "IC8") (pin "10") (pinfunction "RHPOUT_10") (pintype "bidirectional"))
    )
    (net (code "130") (name "unconnected-(J3-2-PadP2)") (class "Default")
      (node (ref "J3") (pin "P2") (pinfunction "2_P2") (pintype "passive"))
    )
    (net (code "131") (name "unconnected-(J4-2-PadP2)") (class "Default")
      (node (ref "J4") (pin "P2") (pinfunction "2_P2") (pintype "passive"))
    )
    (net (code "132") (name "unconnected-(J5-2-PadP2)") (class "Default")
      (node (ref "J5") (pin "P2") (pinfunction "2_P2") (pintype "passive"))
    )
    (net (code "133") (name "unconnected-(J6-2-PadP2)") (class "Default")
      (node (ref "J6") (pin "P2") (pinfunction "2_P2") (pintype "passive"))
    )
    (net (code "134") (name "unconnected-(J7-2-PadP2)") (class "Default")
      (node (ref "J7") (pin "P2") (pinfunction "2_P2") (pintype "passive"))
    )
    (net (code "135") (name "unconnected-(J9-2-PadP2)") (class "Default")
      (node (ref "J9") (pin "P2") (pinfunction "2_P2") (pintype "passive"))
    )
    (net (code "136") (name "unconnected-(J10-2-PadP2)") (class "Default")
      (node (ref "J10") (pin "P2") (pinfunction "2_P2") (pintype "passive"))
    )
    (net (code "137") (name "unconnected-(J11-2-PadP2)") (class "Default")
      (node (ref "J11") (pin "P2") (pinfunction "2_P2") (pintype "passive"))
    )
    (net (code "138") (name "unconnected-(J12-2-PadP2)") (class "Default")
      (node (ref "J12") (pin "P2") (pinfunction "2_P2") (pintype "passive"))
    )
    (net (code "139") (name "unconnected-(JP1-Pad2)") (class "Default")
      (node (ref "JP1") (pin "2") (pinfunction "2_2") (pintype "passive"))
    )
    (net (code "140") (name "unconnected-(JP1-Pad3)") (class "Default")
      (node (ref "JP1") (pin "3") (pinfunction "3_3") (pintype "passive"))
    )
    (net (code "141") (name "unconnected-(JP1-Pad6)") (class "Default")
      (node (ref "JP1") (pin "6") (pinfunction "6_6") (pintype "passive"))
    )
    (net (code "142") (name "unconnected-(JP2-Pad7)") (class "Default")
      (node (ref "JP2") (pin "7") (pinfunction "7_7") (pintype "passive"))
    )
    (net (code "143") (name "unconnected-(SW1A-A1-PadP1)") (class "Default")
      (node (ref "SW1") (pin "P1") (pinfunction "A1_P1") (pintype "passive"))
    )
    (net (code "144") (name "unconnected-(SW1A-B1-PadP4)") (class "Default")
      (node (ref "SW1") (pin "P4") (pinfunction "B1_P4") (pintype "passive"))
    )
  )
)
